# QTouchShield.net
KiCad netlist of a schematic drawn in EAGLE
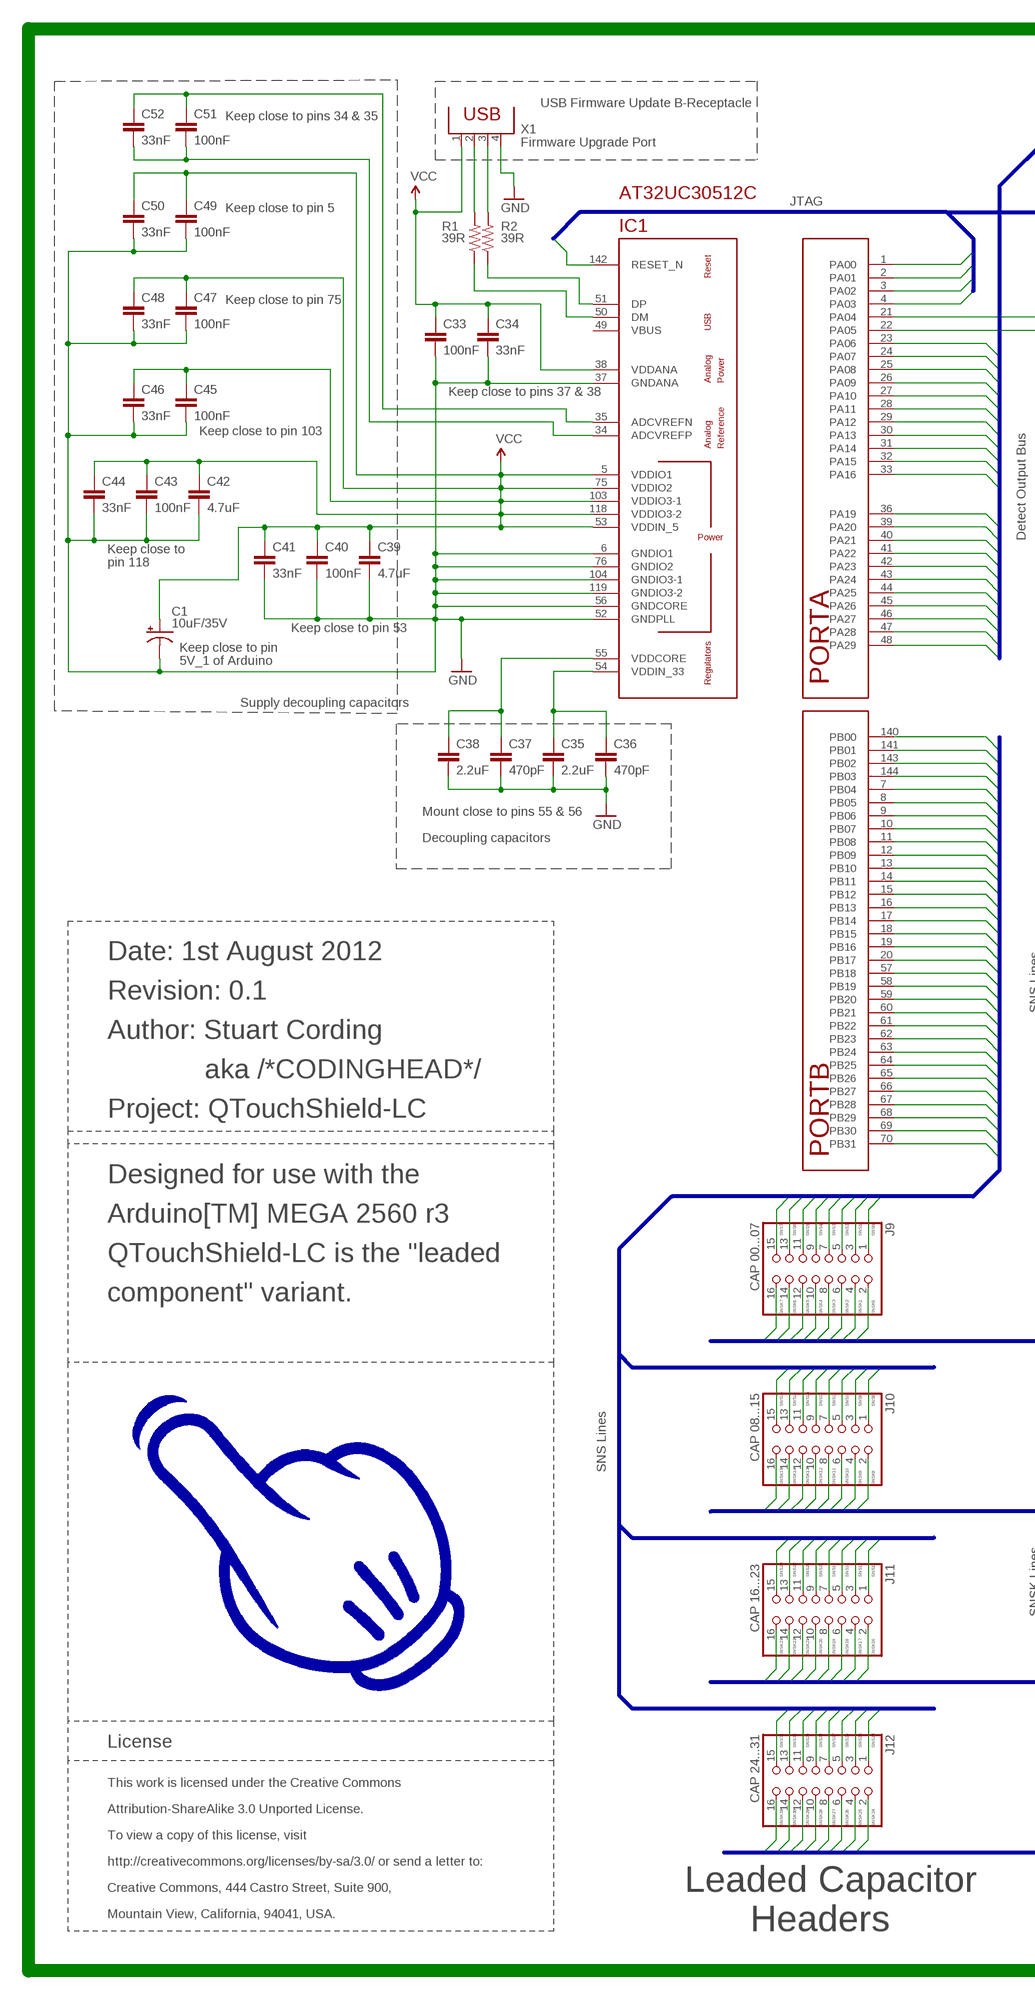
[diagram p0: schematic, sheet 1, part 1 of 2]
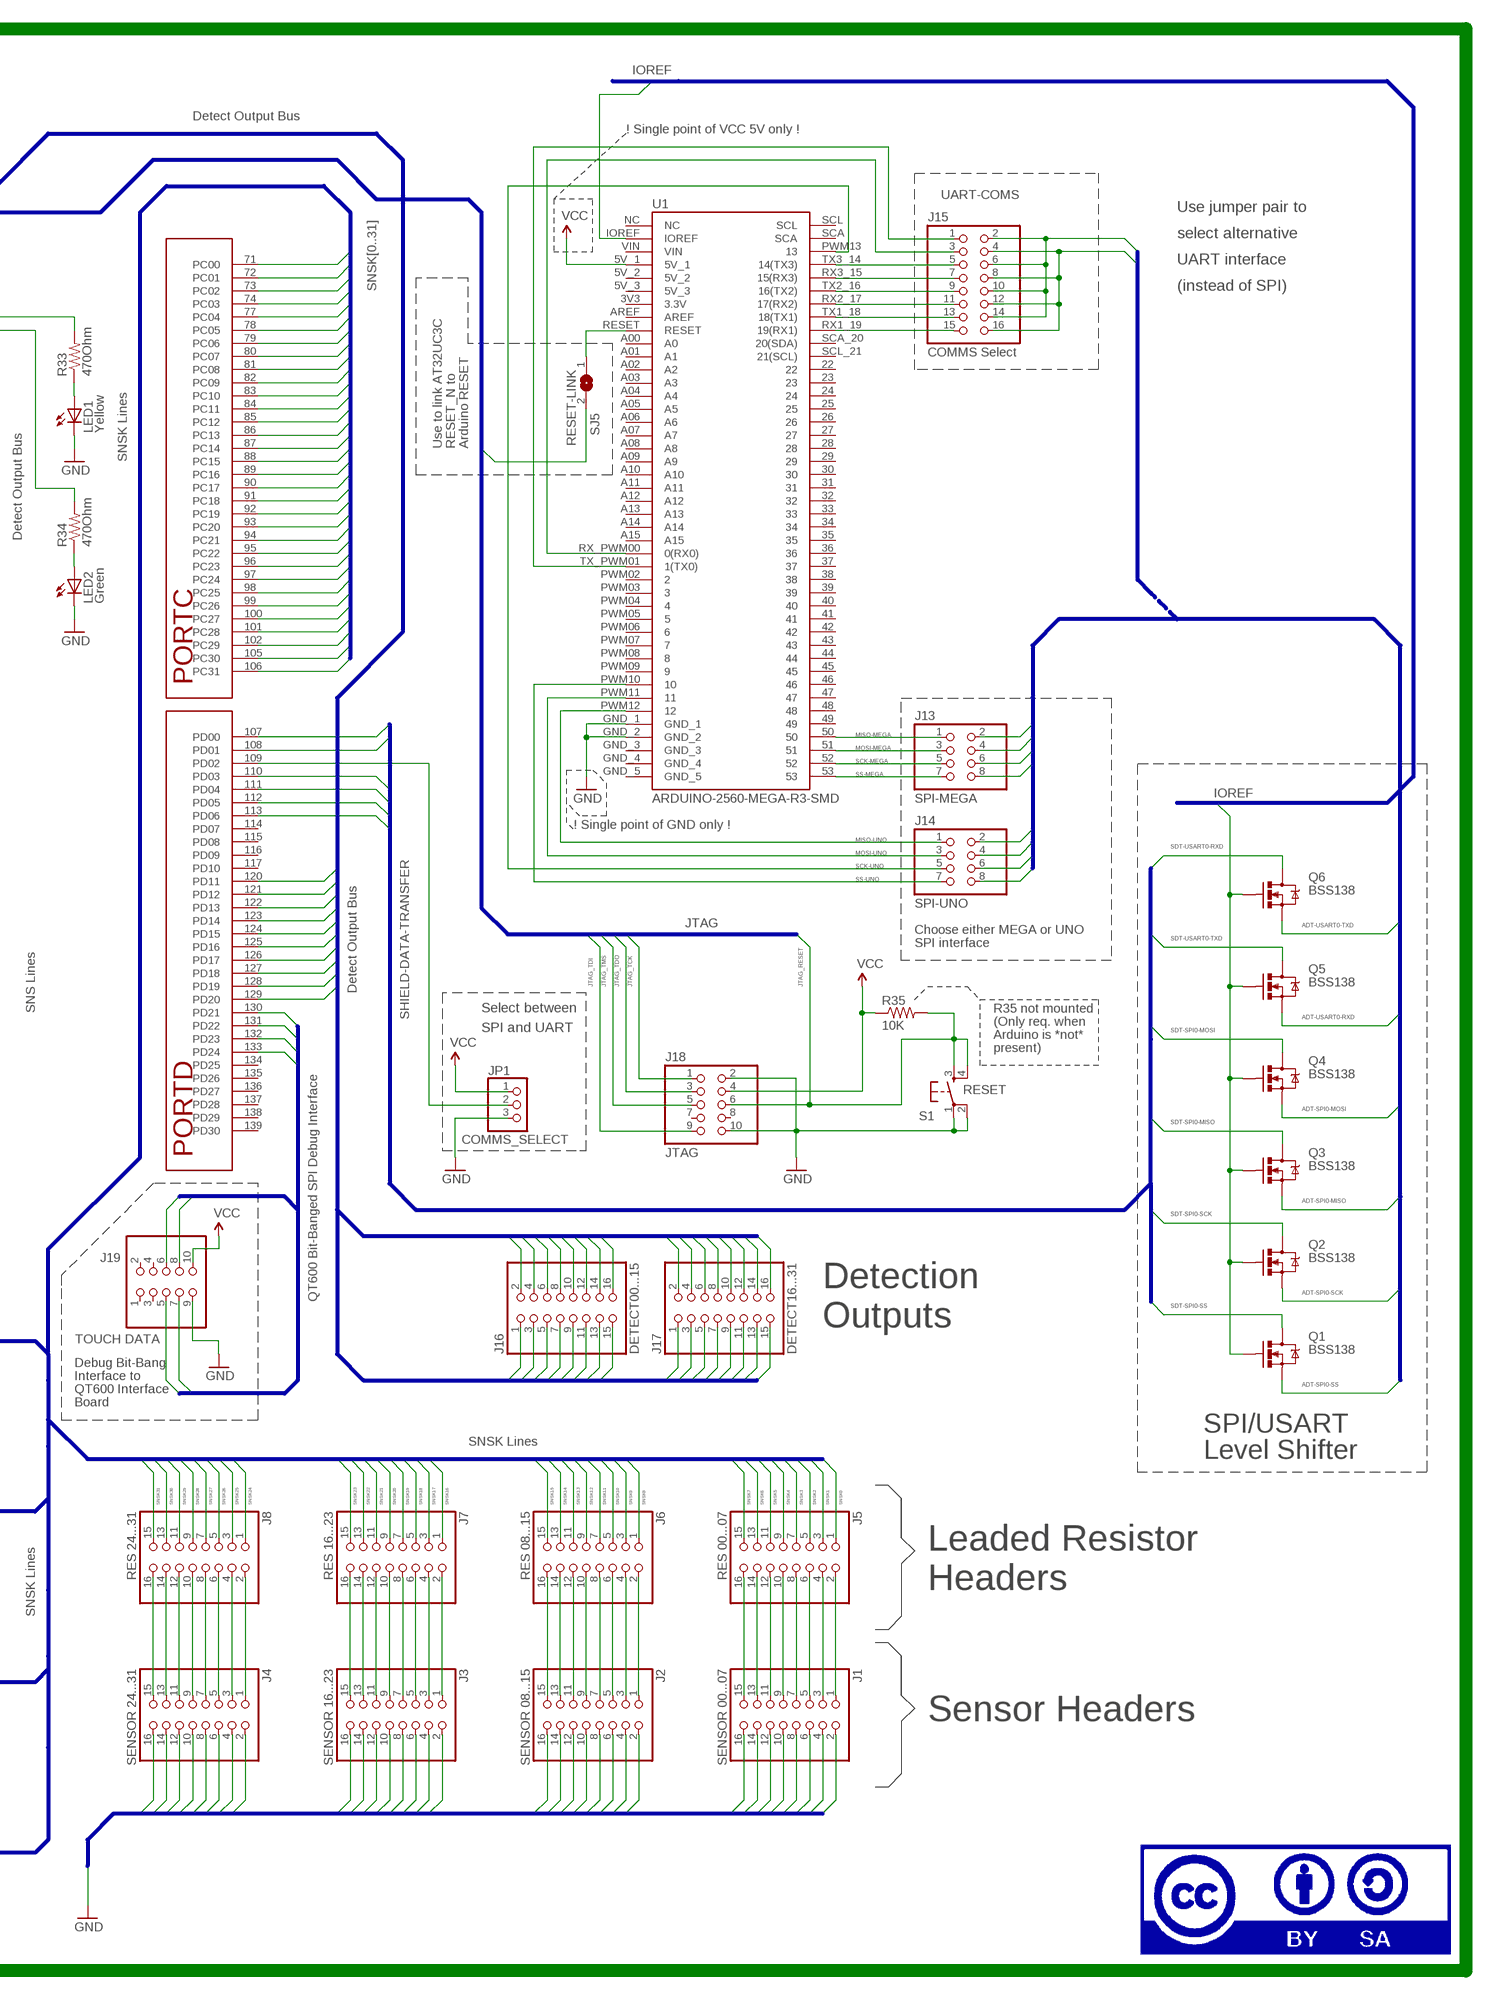
[diagram p1: schematic, sheet 1, part 2 of 2]

(export (version "E")
  (design (tool "Eeschema 10.0.6"))
  (components
    (comp (ref "C1")
      (value "10uF/35V")
      (footprint "eagle-import:PANASONIC_C")
      (libsource (lib "eagle-import") (part "CAP_POLC"))
    )
    (comp (ref "C33")
      (value "100nF")
      (footprint "eagle-import:0805")
      (libsource (lib "eagle-import") (part "CAP0805"))
    )
    (comp (ref "C34")
      (value "33nF")
      (footprint "eagle-import:0805")
      (libsource (lib "eagle-import") (part "CAP0805"))
    )
    (comp (ref "C35")
      (value "2.2uF")
      (footprint "eagle-import:1210")
      (libsource (lib "eagle-import") (part "CAP1210"))
    )
    (comp (ref "C36")
      (value "470pF")
      (footprint "eagle-import:0805")
      (libsource (lib "eagle-import") (part "CAP0805"))
    )
    (comp (ref "C37")
      (value "470pF")
      (footprint "eagle-import:0805")
      (libsource (lib "eagle-import") (part "CAP0805"))
    )
    (comp (ref "C38")
      (value "2.2uF")
      (footprint "eagle-import:1210")
      (libsource (lib "eagle-import") (part "CAP1210"))
    )
    (comp (ref "C39")
      (value "4.7uF")
      (footprint "eagle-import:1210")
      (libsource (lib "eagle-import") (part "CAP1210"))
    )
    (comp (ref "C40")
      (value "100nF")
      (footprint "eagle-import:0805")
      (libsource (lib "eagle-import") (part "CAP0805"))
    )
    (comp (ref "C41")
      (value "33nF")
      (footprint "eagle-import:0805")
      (libsource (lib "eagle-import") (part "CAP0805"))
    )
    (comp (ref "C42")
      (value "4.7uF")
      (footprint "eagle-import:1210")
      (libsource (lib "eagle-import") (part "CAP1210"))
    )
    (comp (ref "C43")
      (value "100nF")
      (footprint "eagle-import:0805")
      (libsource (lib "eagle-import") (part "CAP0805"))
    )
    (comp (ref "C44")
      (value "33nF")
      (footprint "eagle-import:0805")
      (libsource (lib "eagle-import") (part "CAP0805"))
    )
    (comp (ref "C45")
      (value "100nF")
      (footprint "eagle-import:0805")
      (libsource (lib "eagle-import") (part "CAP0805"))
    )
    (comp (ref "C46")
      (value "33nF")
      (footprint "eagle-import:0805")
      (libsource (lib "eagle-import") (part "CAP0805"))
    )
    (comp (ref "C47")
      (value "100nF")
      (footprint "eagle-import:0805")
      (libsource (lib "eagle-import") (part "CAP0805"))
    )
    (comp (ref "C48")
      (value "33nF")
      (footprint "eagle-import:0805")
      (libsource (lib "eagle-import") (part "CAP0805"))
    )
    (comp (ref "C49")
      (value "100nF")
      (footprint "eagle-import:0805")
      (libsource (lib "eagle-import") (part "CAP0805"))
    )
    (comp (ref "C50")
      (value "33nF")
      (footprint "eagle-import:0805")
      (libsource (lib "eagle-import") (part "CAP0805"))
    )
    (comp (ref "C51")
      (value "100nF")
      (footprint "eagle-import:0805")
      (libsource (lib "eagle-import") (part "CAP0805"))
    )
    (comp (ref "C52")
      (value "33nF")
      (footprint "eagle-import:0805")
      (libsource (lib "eagle-import") (part "CAP0805"))
    )
    (comp (ref "IC1")
      (value "AT32UC3C0512CJEDEC-MS-026")
      (footprint "eagle-import:LQFP144")
      (libsource (lib "eagle-import") (part "AT32UC3C0512CJEDEC-MS-026"))
    )
    (comp (ref "J1")
      (value "SENSOR 00...07")
      (footprint "eagle-import:2X8-V-MALE-SMT-HARWIN")
      (libsource (lib "eagle-import") (part "2X8-HEADERHARWIN-PIN-SMT"))
    )
    (comp (ref "J2")
      (value "SENSOR 08...15")
      (footprint "eagle-import:2X8-V-MALE-SMT-HARWIN")
      (libsource (lib "eagle-import") (part "2X8-HEADERHARWIN-PIN-SMT"))
    )
    (comp (ref "J3")
      (value "SENSOR 16...23")
      (footprint "eagle-import:2X8-V-MALE-SMT-HARWIN")
      (libsource (lib "eagle-import") (part "2X8-HEADERHARWIN-PIN-SMT"))
    )
    (comp (ref "J4")
      (value "SENSOR 24...31")
      (footprint "eagle-import:2X8-V-MALE-SMT-HARWIN")
      (libsource (lib "eagle-import") (part "2X8-HEADERHARWIN-PIN-SMT"))
    )
    (comp (ref "J5")
      (value "RES 00...07")
      (footprint "eagle-import:2X8-V-FEMALE-SMT-HARWIN")
      (libsource (lib "eagle-import") (part "2X8-HEADERHARWIN-RECEPTACLE-SMT"))
    )
    (comp (ref "J6")
      (value "RES 08...15")
      (footprint "eagle-import:2X8-V-FEMALE-SMT-HARWIN")
      (libsource (lib "eagle-import") (part "2X8-HEADERHARWIN-RECEPTACLE-SMT"))
    )
    (comp (ref "J7")
      (value "RES 16...23")
      (footprint "eagle-import:2X8-V-FEMALE-SMT-HARWIN")
      (libsource (lib "eagle-import") (part "2X8-HEADERHARWIN-RECEPTACLE-SMT"))
    )
    (comp (ref "J8")
      (value "RES 24...31")
      (footprint "eagle-import:2X8-V-FEMALE-SMT-HARWIN")
      (libsource (lib "eagle-import") (part "2X8-HEADERHARWIN-RECEPTACLE-SMT"))
    )
    (comp (ref "J9")
      (value "CAP 00...07")
      (footprint "eagle-import:2X8-V-FEMALE-SMT-HARWIN")
      (libsource (lib "eagle-import") (part "2X8-HEADERHARWIN-RECEPTACLE-SMT"))
    )
    (comp (ref "J10")
      (value "CAP 08...15")
      (footprint "eagle-import:2X8-V-FEMALE-SMT-HARWIN")
      (libsource (lib "eagle-import") (part "2X8-HEADERHARWIN-RECEPTACLE-SMT"))
    )
    (comp (ref "J11")
      (value "CAP 16...23")
      (footprint "eagle-import:2X8-V-FEMALE-SMT-HARWIN")
      (libsource (lib "eagle-import") (part "2X8-HEADERHARWIN-RECEPTACLE-SMT"))
    )
    (comp (ref "J12")
      (value "CAP 24...31")
      (footprint "eagle-import:2X8-V-FEMALE-SMT-HARWIN")
      (libsource (lib "eagle-import") (part "2X8-HEADERHARWIN-RECEPTACLE-SMT"))
    )
    (comp (ref "J13")
      (value "SPI-MEGA")
      (footprint "eagle-import:2X4-V-MALE-SMT-HARWIN")
      (libsource (lib "eagle-import") (part "2X4-HEADERSMT-MALE"))
    )
    (comp (ref "J14")
      (value "SPI-UNO")
      (footprint "eagle-import:2X4-V-MALE-SMT-HARWIN")
      (libsource (lib "eagle-import") (part "2X4-HEADERSMT-MALE"))
    )
    (comp (ref "J15")
      (value "COMMS Select")
      (footprint "eagle-import:2X8-V-MALE-SMT-HARWIN")
      (libsource (lib "eagle-import") (part "2X8-HEADERHARWIN-PIN-SMT"))
    )
    (comp (ref "J16")
      (value "DETECT00...15")
      (footprint "eagle-import:2X8-V-MALE-SMT-HARWIN")
      (libsource (lib "eagle-import") (part "2X8-HEADERHARWIN-PIN-SMT"))
    )
    (comp (ref "J17")
      (value "DETECT16...31")
      (footprint "eagle-import:2X8-V-MALE-SMT-HARWIN")
      (libsource (lib "eagle-import") (part "2X8-HEADERHARWIN-PIN-SMT"))
    )
    (comp (ref "J18")
      (value "JTAG")
      (footprint "eagle-import:2X5-V-MALE-SMT-HARWIN")
      (libsource (lib "eagle-import") (part "2X5-HEADERSMT"))
    )
    (comp (ref "J19")
      (value "TOUCH DATA")
      (footprint "eagle-import:2X5-V-MALE-SMT-HARWIN")
      (libsource (lib "eagle-import") (part "2X5-HEADERSMT"))
    )
    (comp (ref "JP1")
      (value "COMMS_SELECT")
      (footprint "eagle-import:1X03")
      (libsource (lib "eagle-import") (part "PINHD-1X3"))
    )
    (comp (ref "LED1")
      (value "Yellow")
      (footprint "eagle-import:LED-1206")
      (libsource (lib "eagle-import") (part "LED1206"))
    )
    (comp (ref "LED2")
      (value "Green")
      (footprint "eagle-import:LED-1206")
      (libsource (lib "eagle-import") (part "LED1206"))
    )
    (comp (ref "Q1")
      (value "BSS138")
      (footprint "eagle-import:SOT23-3")
      (libsource (lib "eagle-import") (part "MOSFET-NCHANNELSMD"))
    )
    (comp (ref "Q2")
      (value "BSS138")
      (footprint "eagle-import:SOT23-3")
      (libsource (lib "eagle-import") (part "MOSFET-NCHANNELSMD"))
    )
    (comp (ref "Q3")
      (value "BSS138")
      (footprint "eagle-import:SOT23-3")
      (libsource (lib "eagle-import") (part "MOSFET-NCHANNELSMD"))
    )
    (comp (ref "Q4")
      (value "BSS138")
      (footprint "eagle-import:SOT23-3")
      (libsource (lib "eagle-import") (part "MOSFET-NCHANNELSMD"))
    )
    (comp (ref "Q5")
      (value "BSS138")
      (footprint "eagle-import:SOT23-3")
      (libsource (lib "eagle-import") (part "MOSFET-NCHANNELSMD"))
    )
    (comp (ref "Q6")
      (value "BSS138")
      (footprint "eagle-import:SOT23-3")
      (libsource (lib "eagle-import") (part "MOSFET-NCHANNELSMD"))
    )
    (comp (ref "R1")
      (value "39R")
      (footprint "eagle-import:0805")
      (libsource (lib "eagle-import") (part "RESISTOR0805-RES"))
    )
    (comp (ref "R2")
      (value "39R")
      (footprint "eagle-import:0805")
      (libsource (lib "eagle-import") (part "RESISTOR0805-RES"))
    )
    (comp (ref "R33")
      (value "470Ohm")
      (footprint "eagle-import:0805")
      (libsource (lib "eagle-import") (part "RESISTOR0805-RES"))
    )
    (comp (ref "R34")
      (value "470Ohm")
      (footprint "eagle-import:0805")
      (libsource (lib "eagle-import") (part "RESISTOR0805-RES"))
    )
    (comp (ref "R35")
      (value "10K")
      (footprint "eagle-import:0805")
      (libsource (lib "eagle-import") (part "RESISTOR0805-RES"))
    )
    (comp (ref "S1")
      (value "RESET")
      (footprint "eagle-import:TACTILE_SWITCH_SMD")
      (libsource (lib "eagle-import") (part "TAC_SWITCHSMD"))
    )
    (comp (ref "SJ5")
      (value "RESET-LINK")
      (footprint "eagle-import:SJ")
      (libsource (lib "eagle-import") (part "SJ"))
    )
    (comp (ref "U1")
      (value "ARDUINO-2560-MEGA-R3-SMD")
      (footprint "eagle-import:ARDUINO-2560-R3-SMD")
      (libsource (lib "eagle-import") (part "ARDUINO-2560-MEGA-R3SMD-BOTTOMSMD"))
    )
    (comp (ref "X1")
      (value "Firmware Upgrade Port")
      (footprint "eagle-import:PN87520")
      (libsource (lib "eagle-import") (part "PN87520"))
    )
  )
  (nets
    (net (code "1") (name "/ADT-SPI0-MISO") (class "Default")
      (node (ref "J13") (pin "2") (pinfunction "2_2") (pintype "passive"))
      (node (ref "J14") (pin "2") (pinfunction "2_2") (pintype "passive"))
      (node (ref "Q3") (pin "2") (pinfunction "S_2") (pintype "passive"))
    )
    (net (code "2") (name "/ADT-SPI0-MOSI") (class "Default")
      (node (ref "J13") (pin "4") (pinfunction "4_4") (pintype "passive"))
      (node (ref "J14") (pin "4") (pinfunction "4_4") (pintype "passive"))
      (node (ref "Q4") (pin "2") (pinfunction "S_2") (pintype "passive"))
    )
    (net (code "3") (name "/ADT-SPI0-SCK") (class "Default")
      (node (ref "J13") (pin "6") (pinfunction "6_6") (pintype "passive"))
      (node (ref "J14") (pin "6") (pinfunction "6_6") (pintype "passive"))
      (node (ref "Q2") (pin "2") (pinfunction "S_2") (pintype "passive"))
    )
    (net (code "4") (name "/ADT-SPI0-SS") (class "Default")
      (node (ref "J13") (pin "8") (pinfunction "8_8") (pintype "passive"))
      (node (ref "J14") (pin "8") (pinfunction "8_8") (pintype "passive"))
      (node (ref "Q1") (pin "2") (pinfunction "S_2") (pintype "passive"))
    )
    (net (code "5") (name "/ADT-USART0-RXD") (class "Default")
      (node (ref "J15") (pin "12") (pinfunction "12_12") (pintype "passive"))
      (node (ref "J15") (pin "16") (pinfunction "16_16") (pintype "passive"))
      (node (ref "J15") (pin "4") (pinfunction "4_4") (pintype "passive"))
      (node (ref "J15") (pin "8") (pinfunction "8_8") (pintype "passive"))
      (node (ref "Q5") (pin "2") (pinfunction "S_2") (pintype "passive"))
    )
    (net (code "6") (name "/ADT-USART0-TXD") (class "Default")
      (node (ref "J15") (pin "10") (pinfunction "10_10") (pintype "passive"))
      (node (ref "J15") (pin "14") (pinfunction "14_14") (pintype "passive"))
      (node (ref "J15") (pin "2") (pinfunction "2_2") (pintype "passive"))
      (node (ref "J15") (pin "6") (pinfunction "6_6") (pintype "passive"))
      (node (ref "Q6") (pin "2") (pinfunction "S_2") (pintype "passive"))
    )
    (net (code "7") (name "/IOREF") (class "Default")
      (node (ref "Q1") (pin "1") (pinfunction "G_1") (pintype "passive"))
      (node (ref "Q2") (pin "1") (pinfunction "G_1") (pintype "passive"))
      (node (ref "Q3") (pin "1") (pinfunction "G_1") (pintype "passive"))
      (node (ref "Q4") (pin "1") (pinfunction "G_1") (pintype "passive"))
      (node (ref "Q5") (pin "1") (pinfunction "G_1") (pintype "passive"))
      (node (ref "Q6") (pin "1") (pinfunction "G_1") (pintype "passive"))
      (node (ref "U1") (pin "IOREF") (pinfunction "IOREF_IOREF") (pintype "bidirectional"))
    )
    (net (code "8") (name "/JTAG_RESET") (class "Default")
      (node (ref "IC1") (pin "142") (pinfunction "RESET_N_142") (pintype "input"))
      (node (ref "J18") (pin "6") (pinfunction "6_6") (pintype "passive"))
      (node (ref "R35") (pin "2") (pinfunction "2_2") (pintype "passive"))
      (node (ref "S1") (pin "3") (pinfunction "3_3") (pintype "passive"))
      (node (ref "S1") (pin "4") (pinfunction "4_4") (pintype "passive"))
      (node (ref "SJ5") (pin "2") (pinfunction "2_2") (pintype "passive"))
    )
    (net (code "9") (name "/JTAG_TCK") (class "Default")
      (node (ref "IC1") (pin "1") (pinfunction "PA00_1") (pintype "bidirectional"))
      (node (ref "J18") (pin "1") (pinfunction "1_1") (pintype "passive"))
    )
    (net (code "10") (name "/JTAG_TDI") (class "Default")
      (node (ref "IC1") (pin "2") (pinfunction "PA01_2") (pintype "bidirectional"))
      (node (ref "J18") (pin "9") (pinfunction "9_9") (pintype "passive"))
    )
    (net (code "11") (name "/JTAG_TDO") (class "Default")
      (node (ref "IC1") (pin "3") (pinfunction "PA02_3") (pintype "bidirectional"))
      (node (ref "J18") (pin "3") (pinfunction "3_3") (pintype "passive"))
    )
    (net (code "12") (name "/JTAG_TMS") (class "Default")
      (node (ref "IC1") (pin "4") (pinfunction "PA03_4") (pintype "bidirectional"))
      (node (ref "J18") (pin "5") (pinfunction "5_5") (pintype "passive"))
    )
    (net (code "13") (name "/MISO-MEGA") (class "Default")
      (node (ref "J13") (pin "1") (pinfunction "1_1") (pintype "passive"))
      (node (ref "U1") (pin "50") (pinfunction "50_50") (pintype "bidirectional"))
    )
    (net (code "14") (name "/MISO-UNO") (class "Default")
      (node (ref "J14") (pin "1") (pinfunction "1_1") (pintype "passive"))
      (node (ref "U1") (pin "PWM12") (pinfunction "12_PWM12") (pintype "bidirectional"))
    )
    (net (code "15") (name "/MOSI-MEGA") (class "Default")
      (node (ref "J13") (pin "3") (pinfunction "3_3") (pintype "passive"))
      (node (ref "U1") (pin "51") (pinfunction "51_51") (pintype "bidirectional"))
    )
    (net (code "16") (name "/MOSI-UNO") (class "Default")
      (node (ref "J14") (pin "3") (pinfunction "3_3") (pintype "passive"))
      (node (ref "U1") (pin "PWM11") (pinfunction "11_PWM11") (pintype "bidirectional"))
    )
    (net (code "17") (name "/SCK-MEGA") (class "Default")
      (node (ref "J13") (pin "5") (pinfunction "5_5") (pintype "passive"))
      (node (ref "U1") (pin "52") (pinfunction "52_52") (pintype "bidirectional"))
    )
    (net (code "18") (name "/SCK-UNO") (class "Default")
      (node (ref "J14") (pin "5") (pinfunction "5_5") (pintype "passive"))
      (node (ref "U1") (pin "PWM13") (pinfunction "13_PWM13") (pintype "bidirectional"))
    )
    (net (code "19") (name "/SDT-SPI0-MISO") (class "Default")
      (node (ref "IC1") (pin "112") (pinfunction "PD05_112") (pintype "bidirectional"))
      (node (ref "Q3") (pin "3") (pinfunction "D_3") (pintype "passive"))
    )
    (net (code "20") (name "/SDT-SPI0-MOSI") (class "Default")
      (node (ref "IC1") (pin "111") (pinfunction "PD04_111") (pintype "bidirectional"))
      (node (ref "Q4") (pin "3") (pinfunction "D_3") (pintype "passive"))
    )
    (net (code "21") (name "/SDT-SPI0-SCK") (class "Default")
      (node (ref "IC1") (pin "113") (pinfunction "PD06_113") (pintype "bidirectional"))
      (node (ref "Q2") (pin "3") (pinfunction "D_3") (pintype "passive"))
    )
    (net (code "22") (name "/SDT-SPI0-SS") (class "Default")
      (node (ref "IC1") (pin "110") (pinfunction "PD03_110") (pintype "bidirectional"))
      (node (ref "Q1") (pin "3") (pinfunction "D_3") (pintype "passive"))
    )
    (net (code "23") (name "/SDT-USART0-RXD") (class "Default")
      (node (ref "IC1") (pin "108") (pinfunction "PD01_108") (pintype "bidirectional"))
      (node (ref "Q6") (pin "3") (pinfunction "D_3") (pintype "passive"))
    )
    (net (code "24") (name "/SDT-USART0-TXD") (class "Default")
      (node (ref "IC1") (pin "107") (pinfunction "PD00_107") (pintype "bidirectional"))
      (node (ref "Q5") (pin "3") (pinfunction "D_3") (pintype "passive"))
    )
    (net (code "25") (name "/SHIELD-DETECT0") (class "Default")
      (node (ref "IC1") (pin "23") (pinfunction "PA06_23") (pintype "bidirectional"))
      (node (ref "J16") (pin "1") (pinfunction "1_1") (pintype "passive"))
    )
    (net (code "26") (name "/SHIELD-DETECT1") (class "Default")
      (node (ref "IC1") (pin "24") (pinfunction "PA07_24") (pintype "bidirectional"))
      (node (ref "J16") (pin "2") (pinfunction "2_2") (pintype "passive"))
    )
    (net (code "27") (name "/SHIELD-DETECT2") (class "Default")
      (node (ref "IC1") (pin "25") (pinfunction "PA08_25") (pintype "bidirectional"))
      (node (ref "J16") (pin "3") (pinfunction "3_3") (pintype "passive"))
    )
    (net (code "28") (name "/SHIELD-DETECT3") (class "Default")
      (node (ref "IC1") (pin "26") (pinfunction "PA09_26") (pintype "bidirectional"))
      (node (ref "J16") (pin "4") (pinfunction "4_4") (pintype "passive"))
    )
    (net (code "29") (name "/SHIELD-DETECT4") (class "Default")
      (node (ref "IC1") (pin "27") (pinfunction "PA10_27") (pintype "bidirectional"))
      (node (ref "J16") (pin "5") (pinfunction "5_5") (pintype "passive"))
    )
    (net (code "30") (name "/SHIELD-DETECT5") (class "Default")
      (node (ref "IC1") (pin "28") (pinfunction "PA11_28") (pintype "bidirectional"))
      (node (ref "J16") (pin "6") (pinfunction "6_6") (pintype "passive"))
    )
    (net (code "31") (name "/SHIELD-DETECT6") (class "Default")
      (node (ref "IC1") (pin "29") (pinfunction "PA12_29") (pintype "bidirectional"))
      (node (ref "J16") (pin "7") (pinfunction "7_7") (pintype "passive"))
    )
    (net (code "32") (name "/SHIELD-DETECT7") (class "Default")
      (node (ref "IC1") (pin "30") (pinfunction "PA13_30") (pintype "bidirectional"))
      (node (ref "J16") (pin "8") (pinfunction "8_8") (pintype "passive"))
    )
    (net (code "33") (name "/SHIELD-DETECT8") (class "Default")
      (node (ref "IC1") (pin "31") (pinfunction "PA14_31") (pintype "bidirectional"))
      (node (ref "J16") (pin "9") (pinfunction "9_9") (pintype "passive"))
    )
    (net (code "34") (name "/SHIELD-DETECT9") (class "Default")
      (node (ref "IC1") (pin "32") (pinfunction "PA15_32") (pintype "bidirectional"))
      (node (ref "J16") (pin "10") (pinfunction "10_10") (pintype "passive"))
    )
    (net (code "35") (name "/SHIELD-DETECT10") (class "Default")
      (node (ref "IC1") (pin "33") (pinfunction "PA16_33") (pintype "bidirectional"))
      (node (ref "J16") (pin "11") (pinfunction "11_11") (pintype "passive"))
    )
    (net (code "36") (name "/SHIELD-DETECT11") (class "Default")
      (node (ref "IC1") (pin "36") (pinfunction "PA19_36") (pintype "bidirectional"))
      (node (ref "J16") (pin "12") (pinfunction "12_12") (pintype "passive"))
    )
    (net (code "37") (name "/SHIELD-DETECT12") (class "Default")
      (node (ref "IC1") (pin "39") (pinfunction "PA20_39") (pintype "bidirectional"))
      (node (ref "J16") (pin "13") (pinfunction "13_13") (pintype "passive"))
    )
    (net (code "38") (name "/SHIELD-DETECT13") (class "Default")
      (node (ref "IC1") (pin "40") (pinfunction "PA21_40") (pintype "bidirectional"))
      (node (ref "J16") (pin "14") (pinfunction "14_14") (pintype "passive"))
    )
    (net (code "39") (name "/SHIELD-DETECT14") (class "Default")
      (node (ref "IC1") (pin "41") (pinfunction "PA22_41") (pintype "bidirectional"))
      (node (ref "J16") (pin "15") (pinfunction "15_15") (pintype "passive"))
    )
    (net (code "40") (name "/SHIELD-DETECT15") (class "Default")
      (node (ref "IC1") (pin "42") (pinfunction "PA23_42") (pintype "bidirectional"))
      (node (ref "J16") (pin "16") (pinfunction "16_16") (pintype "passive"))
    )
    (net (code "41") (name "/SHIELD-DETECT16") (class "Default")
      (node (ref "IC1") (pin "43") (pinfunction "PA24_43") (pintype "bidirectional"))
      (node (ref "J17") (pin "15") (pinfunction "15_15") (pintype "passive"))
    )
    (net (code "42") (name "/SHIELD-DETECT17") (class "Default")
      (node (ref "IC1") (pin "44") (pinfunction "PA25_44") (pintype "bidirectional"))
      (node (ref "J17") (pin "16") (pinfunction "16_16") (pintype "passive"))
    )
    (net (code "43") (name "/SHIELD-DETECT18") (class "Default")
      (node (ref "IC1") (pin "45") (pinfunction "PA26_45") (pintype "bidirectional"))
      (node (ref "J17") (pin "13") (pinfunction "13_13") (pintype "passive"))
    )
    (net (code "44") (name "/SHIELD-DETECT19") (class "Default")
      (node (ref "IC1") (pin "46") (pinfunction "PA27_46") (pintype "bidirectional"))
      (node (ref "J17") (pin "14") (pinfunction "14_14") (pintype "passive"))
    )
    (net (code "45") (name "/SHIELD-DETECT20") (class "Default")
      (node (ref "IC1") (pin "47") (pinfunction "PA28_47") (pintype "bidirectional"))
      (node (ref "J17") (pin "11") (pinfunction "11_11") (pintype "passive"))
    )
    (net (code "46") (name "/SHIELD-DETECT21") (class "Default")
      (node (ref "IC1") (pin "48") (pinfunction "PA29_48") (pintype "bidirectional"))
      (node (ref "J17") (pin "12") (pinfunction "12_12") (pintype "passive"))
    )
    (net (code "47") (name "/SHIELD-DETECT22") (class "Default")
      (node (ref "IC1") (pin "120") (pinfunction "PD11_120") (pintype "bidirectional"))
      (node (ref "J17") (pin "9") (pinfunction "9_9") (pintype "passive"))
    )
    (net (code "48") (name "/SHIELD-DETECT23") (class "Default")
      (node (ref "IC1") (pin "121") (pinfunction "PD12_121") (pintype "bidirectional"))
      (node (ref "J17") (pin "10") (pinfunction "10_10") (pintype "passive"))
    )
    (net (code "49") (name "/SHIELD-DETECT24") (class "Default")
      (node (ref "IC1") (pin "122") (pinfunction "PD13_122") (pintype "bidirectional"))
      (node (ref "J17") (pin "7") (pinfunction "7_7") (pintype "passive"))
    )
    (net (code "50") (name "/SHIELD-DETECT25") (class "Default")
      (node (ref "IC1") (pin "123") (pinfunction "PD14_123") (pintype "bidirectional"))
      (node (ref "J17") (pin "8") (pinfunction "8_8") (pintype "passive"))
    )
    (net (code "51") (name "/SHIELD-DETECT26") (class "Default")
      (node (ref "IC1") (pin "124") (pinfunction "PD15_124") (pintype "bidirectional"))
      (node (ref "J17") (pin "5") (pinfunction "5_5") (pintype "passive"))
    )
    (net (code "52") (name "/SHIELD-DETECT27") (class "Default")
      (node (ref "IC1") (pin "125") (pinfunction "PD16_125") (pintype "bidirectional"))
      (node (ref "J17") (pin "6") (pinfunction "6_6") (pintype "passive"))
    )
    (net (code "53") (name "/SHIELD-DETECT28") (class "Default")
      (node (ref "IC1") (pin "126") (pinfunction "PD17_126") (pintype "bidirectional"))
      (node (ref "J17") (pin "3") (pinfunction "3_3") (pintype "passive"))
    )
    (net (code "54") (name "/SHIELD-DETECT29") (class "Default")
      (node (ref "IC1") (pin "127") (pinfunction "PD18_127") (pintype "bidirectional"))
      (node (ref "J17") (pin "4") (pinfunction "4_4") (pintype "passive"))
    )
    (net (code "55") (name "/SHIELD-DETECT30") (class "Default")
      (node (ref "IC1") (pin "128") (pinfunction "PD19_128") (pintype "bidirectional"))
      (node (ref "J17") (pin "1") (pinfunction "1_1") (pintype "passive"))
    )
    (net (code "56") (name "/SHIELD-DETECT31") (class "Default")
      (node (ref "IC1") (pin "129") (pinfunction "PD20_129") (pintype "bidirectional"))
      (node (ref "J17") (pin "2") (pinfunction "2_2") (pintype "passive"))
    )
    (net (code "57") (name "/SNS0") (class "Default")
      (node (ref "IC1") (pin "140") (pinfunction "PB00_140") (pintype "bidirectional"))
      (node (ref "J9") (pin "1") (pinfunction "1_1") (pintype "passive"))
    )
    (net (code "58") (name "/SNS1") (class "Default")
      (node (ref "IC1") (pin "141") (pinfunction "PB01_141") (pintype "bidirectional"))
      (node (ref "J9") (pin "3") (pinfunction "3_3") (pintype "passive"))
    )
    (net (code "59") (name "/SNS2") (class "Default")
      (node (ref "IC1") (pin "143") (pinfunction "PB02_143") (pintype "bidirectional"))
      (node (ref "J9") (pin "5") (pinfunction "5_5") (pintype "passive"))
    )
    (net (code "60") (name "/SNS3") (class "Default")
      (node (ref "IC1") (pin "144") (pinfunction "PB03_144") (pintype "bidirectional"))
      (node (ref "J9") (pin "7") (pinfunction "7_7") (pintype "passive"))
    )
    (net (code "61") (name "/SNS4") (class "Default")
      (node (ref "IC1") (pin "7") (pinfunction "PB04_7") (pintype "bidirectional"))
      (node (ref "J9") (pin "9") (pinfunction "9_9") (pintype "passive"))
    )
    (net (code "62") (name "/SNS5") (class "Default")
      (node (ref "IC1") (pin "8") (pinfunction "PB05_8") (pintype "bidirectional"))
      (node (ref "J9") (pin "11") (pinfunction "11_11") (pintype "passive"))
    )
    (net (code "63") (name "/SNS6") (class "Default")
      (node (ref "IC1") (pin "9") (pinfunction "PB06_9") (pintype "bidirectional"))
      (node (ref "J9") (pin "13") (pinfunction "13_13") (pintype "passive"))
    )
    (net (code "64") (name "/SNS7") (class "Default")
      (node (ref "IC1") (pin "10") (pinfunction "PB07_10") (pintype "bidirectional"))
      (node (ref "J9") (pin "15") (pinfunction "15_15") (pintype "passive"))
    )
    (net (code "65") (name "/SNS8") (class "Default")
      (node (ref "IC1") (pin "11") (pinfunction "PB08_11") (pintype "bidirectional"))
      (node (ref "J10") (pin "1") (pinfunction "1_1") (pintype "passive"))
    )
    (net (code "66") (name "/SNS9") (class "Default")
      (node (ref "IC1") (pin "12") (pinfunction "PB09_12") (pintype "bidirectional"))
      (node (ref "J10") (pin "3") (pinfunction "3_3") (pintype "passive"))
    )
    (net (code "67") (name "/SNS10") (class "Default")
      (node (ref "IC1") (pin "13") (pinfunction "PB10_13") (pintype "bidirectional"))
      (node (ref "J10") (pin "5") (pinfunction "5_5") (pintype "passive"))
    )
    (net (code "68") (name "/SNS11") (class "Default")
      (node (ref "IC1") (pin "14") (pinfunction "PB11_14") (pintype "bidirectional"))
      (node (ref "J10") (pin "7") (pinfunction "7_7") (pintype "passive"))
    )
    (net (code "69") (name "/SNS12") (class "Default")
      (node (ref "IC1") (pin "15") (pinfunction "PB12_15") (pintype "bidirectional"))
      (node (ref "J10") (pin "9") (pinfunction "9_9") (pintype "passive"))
    )
    (net (code "70") (name "/SNS13") (class "Default")
      (node (ref "IC1") (pin "16") (pinfunction "PB13_16") (pintype "bidirectional"))
      (node (ref "J10") (pin "11") (pinfunction "11_11") (pintype "passive"))
    )
    (net (code "71") (name "/SNS14") (class "Default")
      (node (ref "IC1") (pin "17") (pinfunction "PB14_17") (pintype "bidirectional"))
      (node (ref "J10") (pin "13") (pinfunction "13_13") (pintype "passive"))
    )
    (net (code "72") (name "/SNS15") (class "Default")
      (node (ref "IC1") (pin "18") (pinfunction "PB15_18") (pintype "bidirectional"))
      (node (ref "J10") (pin "15") (pinfunction "15_15") (pintype "passive"))
    )
    (net (code "73") (name "/SNS16") (class "Default")
      (node (ref "IC1") (pin "19") (pinfunction "PB16_19") (pintype "bidirectional"))
      (node (ref "J11") (pin "1") (pinfunction "1_1") (pintype "passive"))
    )
    (net (code "74") (name "/SNS17") (class "Default")
      (node (ref "IC1") (pin "20") (pinfunction "PB17_20") (pintype "bidirectional"))
      (node (ref "J11") (pin "3") (pinfunction "3_3") (pintype "passive"))
    )
    (net (code "75") (name "/SNS18") (class "Default")
      (node (ref "IC1") (pin "57") (pinfunction "PB18_57") (pintype "bidirectional"))
      (node (ref "J11") (pin "5") (pinfunction "5_5") (pintype "passive"))
    )
    (net (code "76") (name "/SNS19") (class "Default")
      (node (ref "IC1") (pin "58") (pinfunction "PB19_58") (pintype "bidirectional"))
      (node (ref "J11") (pin "7") (pinfunction "7_7") (pintype "passive"))
    )
    (net (code "77") (name "/SNS20") (class "Default")
      (node (ref "IC1") (pin "59") (pinfunction "PB20_59") (pintype "bidirectional"))
      (node (ref "J11") (pin "9") (pinfunction "9_9") (pintype "passive"))
    )
    (net (code "78") (name "/SNS21") (class "Default")
      (node (ref "IC1") (pin "60") (pinfunction "PB21_60") (pintype "bidirectional"))
      (node (ref "J11") (pin "11") (pinfunction "11_11") (pintype "passive"))
    )
    (net (code "79") (name "/SNS22") (class "Default")
      (node (ref "IC1") (pin "61") (pinfunction "PB22_61") (pintype "bidirectional"))
      (node (ref "J11") (pin "13") (pinfunction "13_13") (pintype "passive"))
    )
    (net (code "80") (name "/SNS23") (class "Default")
      (node (ref "IC1") (pin "62") (pinfunction "PB23_62") (pintype "bidirectional"))
      (node (ref "J11") (pin "15") (pinfunction "15_15") (pintype "passive"))
    )
    (net (code "81") (name "/SNS24") (class "Default")
      (node (ref "IC1") (pin "63") (pinfunction "PB24_63") (pintype "bidirectional"))
      (node (ref "J12") (pin "1") (pinfunction "1_1") (pintype "passive"))
    )
    (net (code "82") (name "/SNS25") (class "Default")
      (node (ref "IC1") (pin "64") (pinfunction "PB25_64") (pintype "bidirectional"))
      (node (ref "J12") (pin "3") (pinfunction "3_3") (pintype "passive"))
    )
    (net (code "83") (name "/SNS26") (class "Default")
      (node (ref "IC1") (pin "65") (pinfunction "PB26_65") (pintype "bidirectional"))
      (node (ref "J12") (pin "5") (pinfunction "5_5") (pintype "passive"))
    )
    (net (code "84") (name "/SNS27") (class "Default")
      (node (ref "IC1") (pin "66") (pinfunction "PB27_66") (pintype "bidirectional"))
      (node (ref "J12") (pin "7") (pinfunction "7_7") (pintype "passive"))
    )
    (net (code "85") (name "/SNS28") (class "Default")
      (node (ref "IC1") (pin "67") (pinfunction "PB28_67") (pintype "bidirectional"))
      (node (ref "J12") (pin "9") (pinfunction "9_9") (pintype "passive"))
    )
    (net (code "86") (name "/SNS29") (class "Default")
      (node (ref "IC1") (pin "68") (pinfunction "PB29_68") (pintype "bidirectional"))
      (node (ref "J12") (pin "11") (pinfunction "11_11") (pintype "passive"))
    )
    (net (code "87") (name "/SNS30") (class "Default")
      (node (ref "IC1") (pin "69") (pinfunction "PB30_69") (pintype "bidirectional"))
      (node (ref "J12") (pin "13") (pinfunction "13_13") (pintype "passive"))
    )
    (net (code "88") (name "/SNS31") (class "Default")
      (node (ref "IC1") (pin "70") (pinfunction "PB31_70") (pintype "bidirectional"))
      (node (ref "J12") (pin "15") (pinfunction "15_15") (pintype "passive"))
    )
    (net (code "89") (name "/SNSK0") (class "Default")
      (node (ref "IC1") (pin "71") (pinfunction "PC00_71") (pintype "bidirectional"))
      (node (ref "J5") (pin "1") (pinfunction "1_1") (pintype "passive"))
      (node (ref "J9") (pin "2") (pinfunction "2_2") (pintype "passive"))
    )
    (net (code "90") (name "/SNSK1") (class "Default")
      (node (ref "IC1") (pin "72") (pinfunction "PC01_72") (pintype "bidirectional"))
      (node (ref "J5") (pin "3") (pinfunction "3_3") (pintype "passive"))
      (node (ref "J9") (pin "4") (pinfunction "4_4") (pintype "passive"))
    )
    (net (code "91") (name "/SNSK2") (class "Default")
      (node (ref "IC1") (pin "73") (pinfunction "PC02_73") (pintype "bidirectional"))
      (node (ref "J5") (pin "5") (pinfunction "5_5") (pintype "passive"))
      (node (ref "J9") (pin "6") (pinfunction "6_6") (pintype "passive"))
    )
    (net (code "92") (name "/SNSK3") (class "Default")
      (node (ref "IC1") (pin "74") (pinfunction "PC03_74") (pintype "bidirectional"))
      (node (ref "J5") (pin "7") (pinfunction "7_7") (pintype "passive"))
      (node (ref "J9") (pin "8") (pinfunction "8_8") (pintype "passive"))
    )
    (net (code "93") (name "/SNSK4") (class "Default")
      (node (ref "IC1") (pin "77") (pinfunction "PC04_77") (pintype "bidirectional"))
      (node (ref "J5") (pin "9") (pinfunction "9_9") (pintype "passive"))
      (node (ref "J9") (pin "10") (pinfunction "10_10") (pintype "passive"))
    )
    (net (code "94") (name "/SNSK5") (class "Default")
      (node (ref "IC1") (pin "78") (pinfunction "PC05_78") (pintype "bidirectional"))
      (node (ref "J5") (pin "11") (pinfunction "11_11") (pintype "passive"))
      (node (ref "J9") (pin "12") (pinfunction "12_12") (pintype "passive"))
    )
    (net (code "95") (name "/SNSK6") (class "Default")
      (node (ref "IC1") (pin "79") (pinfunction "PC06_79") (pintype "bidirectional"))
      (node (ref "J5") (pin "13") (pinfunction "13_13") (pintype "passive"))
      (node (ref "J9") (pin "14") (pinfunction "14_14") (pintype "passive"))
    )
    (net (code "96") (name "/SNSK7") (class "Default")
      (node (ref "IC1") (pin "80") (pinfunction "PC07_80") (pintype "bidirectional"))
      (node (ref "J5") (pin "15") (pinfunction "15_15") (pintype "passive"))
      (node (ref "J9") (pin "16") (pinfunction "16_16") (pintype "passive"))
    )
    (net (code "97") (name "/SNSK8") (class "Default")
      (node (ref "IC1") (pin "81") (pinfunction "PC08_81") (pintype "bidirectional"))
      (node (ref "J10") (pin "2") (pinfunction "2_2") (pintype "passive"))
      (node (ref "J6") (pin "1") (pinfunction "1_1") (pintype "passive"))
    )
    (net (code "98") (name "/SNSK9") (class "Default")
      (node (ref "IC1") (pin "82") (pinfunction "PC09_82") (pintype "bidirectional"))
      (node (ref "J10") (pin "4") (pinfunction "4_4") (pintype "passive"))
      (node (ref "J6") (pin "3") (pinfunction "3_3") (pintype "passive"))
    )
    (net (code "99") (name "/SNSK10") (class "Default")
      (node (ref "IC1") (pin "83") (pinfunction "PC10_83") (pintype "bidirectional"))
      (node (ref "J10") (pin "6") (pinfunction "6_6") (pintype "passive"))
      (node (ref "J6") (pin "5") (pinfunction "5_5") (pintype "passive"))
    )
    (net (code "100") (name "/SNSK11") (class "Default")
      (node (ref "IC1") (pin "84") (pinfunction "PC11_84") (pintype "bidirectional"))
      (node (ref "J10") (pin "8") (pinfunction "8_8") (pintype "passive"))
      (node (ref "J6") (pin "7") (pinfunction "7_7") (pintype "passive"))
    )
    (net (code "101") (name "/SNSK12") (class "Default")
      (node (ref "IC1") (pin "85") (pinfunction "PC12_85") (pintype "bidirectional"))
      (node (ref "J10") (pin "10") (pinfunction "10_10") (pintype "passive"))
      (node (ref "J6") (pin "9") (pinfunction "9_9") (pintype "passive"))
    )
    (net (code "102") (name "/SNSK13") (class "Default")
      (node (ref "IC1") (pin "86") (pinfunction "PC13_86") (pintype "bidirectional"))
      (node (ref "J10") (pin "12") (pinfunction "12_12") (pintype "passive"))
      (node (ref "J6") (pin "11") (pinfunction "11_11") (pintype "passive"))
    )
    (net (code "103") (name "/SNSK14") (class "Default")
      (node (ref "IC1") (pin "87") (pinfunction "PC14_87") (pintype "bidirectional"))
      (node (ref "J10") (pin "14") (pinfunction "14_14") (pintype "passive"))
      (node (ref "J6") (pin "13") (pinfunction "13_13") (pintype "passive"))
    )
    (net (code "104") (name "/SNSK15") (class "Default")
      (node (ref "IC1") (pin "88") (pinfunction "PC15_88") (pintype "bidirectional"))
      (node (ref "J10") (pin "16") (pinfunction "16_16") (pintype "passive"))
      (node (ref "J6") (pin "15") (pinfunction "15_15") (pintype "passive"))
    )
    (net (code "105") (name "/SNSK16") (class "Default")
      (node (ref "IC1") (pin "89") (pinfunction "PC16_89") (pintype "bidirectional"))
      (node (ref "J11") (pin "2") (pinfunction "2_2") (pintype "passive"))
      (node (ref "J7") (pin "1") (pinfunction "1_1") (pintype "passive"))
    )
    (net (code "106") (name "/SNSK17") (class "Default")
      (node (ref "IC1") (pin "90") (pinfunction "PC17_90") (pintype "bidirectional"))
      (node (ref "J11") (pin "4") (pinfunction "4_4") (pintype "passive"))
      (node (ref "J7") (pin "3") (pinfunction "3_3") (pintype "passive"))
    )
    (net (code "107") (name "/SNSK18") (class "Default")
      (node (ref "IC1") (pin "91") (pinfunction "PC18_91") (pintype "bidirectional"))
      (node (ref "J11") (pin "6") (pinfunction "6_6") (pintype "passive"))
      (node (ref "J7") (pin "5") (pinfunction "5_5") (pintype "passive"))
    )
    (net (code "108") (name "/SNSK19") (class "Default")
      (node (ref "IC1") (pin "92") (pinfunction "PC19_92") (pintype "bidirectional"))
      (node (ref "J11") (pin "8") (pinfunction "8_8") (pintype "passive"))
      (node (ref "J7") (pin "7") (pinfunction "7_7") (pintype "passive"))
    )
    (net (code "109") (name "/SNSK20") (class "Default")
      (node (ref "IC1") (pin "93") (pinfunction "PC20_93") (pintype "bidirectional"))
      (node (ref "J11") (pin "10") (pinfunction "10_10") (pintype "passive"))
      (node (ref "J7") (pin "9") (pinfunction "9_9") (pintype "passive"))
    )
    (net (code "110") (name "/SNSK21") (class "Default")
      (node (ref "IC1") (pin "94") (pinfunction "PC21_94") (pintype "bidirectional"))
      (node (ref "J11") (pin "12") (pinfunction "12_12") (pintype "passive"))
      (node (ref "J7") (pin "11") (pinfunction "11_11") (pintype "passive"))
    )
    (net (code "111") (name "/SNSK22") (class "Default")
      (node (ref "IC1") (pin "95") (pinfunction "PC22_95") (pintype "bidirectional"))
      (node (ref "J11") (pin "14") (pinfunction "14_14") (pintype "passive"))
      (node (ref "J7") (pin "13") (pinfunction "13_13") (pintype "passive"))
    )
    (net (code "112") (name "/SNSK23") (class "Default")
      (node (ref "IC1") (pin "96") (pinfunction "PC23_96") (pintype "bidirectional"))
      (node (ref "J11") (pin "16") (pinfunction "16_16") (pintype "passive"))
      (node (ref "J7") (pin "15") (pinfunction "15_15") (pintype "passive"))
    )
    (net (code "113") (name "/SNSK24") (class "Default")
      (node (ref "IC1") (pin "97") (pinfunction "PC24_97") (pintype "bidirectional"))
      (node (ref "J12") (pin "2") (pinfunction "2_2") (pintype "passive"))
      (node (ref "J8") (pin "1") (pinfunction "1_1") (pintype "passive"))
    )
    (net (code "114") (name "/SNSK25") (class "Default")
      (node (ref "IC1") (pin "98") (pinfunction "PC25_98") (pintype "bidirectional"))
      (node (ref "J12") (pin "4") (pinfunction "4_4") (pintype "passive"))
      (node (ref "J8") (pin "3") (pinfunction "3_3") (pintype "passive"))
    )
    (net (code "115") (name "/SNSK26") (class "Default")
      (node (ref "IC1") (pin "99") (pinfunction "PC26_99") (pintype "bidirectional"))
      (node (ref "J12") (pin "6") (pinfunction "6_6") (pintype "passive"))
      (node (ref "J8") (pin "5") (pinfunction "5_5") (pintype "passive"))
    )
    (net (code "116") (name "/SNSK27") (class "Default")
      (node (ref "IC1") (pin "100") (pinfunction "PC27_100") (pintype "bidirectional"))
      (node (ref "J12") (pin "8") (pinfunction "8_8") (pintype "passive"))
      (node (ref "J8") (pin "7") (pinfunction "7_7") (pintype "passive"))
    )
    (net (code "117") (name "/SNSK28") (class "Default")
      (node (ref "IC1") (pin "101") (pinfunction "PC28_101") (pintype "bidirectional"))
      (node (ref "J12") (pin "10") (pinfunction "10_10") (pintype "passive"))
      (node (ref "J8") (pin "9") (pinfunction "9_9") (pintype "passive"))
    )
    (net (code "118") (name "/SNSK29") (class "Default")
      (node (ref "IC1") (pin "102") (pinfunction "PC29_102") (pintype "bidirectional"))
      (node (ref "J12") (pin "12") (pinfunction "12_12") (pintype "passive"))
      (node (ref "J8") (pin "11") (pinfunction "11_11") (pintype "passive"))
    )
    (net (code "119") (name "/SNSK30") (class "Default")
      (node (ref "IC1") (pin "105") (pinfunction "PC30_105") (pintype "bidirectional"))
      (node (ref "J12") (pin "14") (pinfunction "14_14") (pintype "passive"))
      (node (ref "J8") (pin "13") (pinfunction "13_13") (pintype "passive"))
    )
    (net (code "120") (name "/SNSK31") (class "Default")
      (node (ref "IC1") (pin "106") (pinfunction "PC31_106") (pintype "bidirectional"))
      (node (ref "J12") (pin "16") (pinfunction "16_16") (pintype "passive"))
      (node (ref "J8") (pin "15") (pinfunction "15_15") (pintype "passive"))
    )
    (net (code "122") (name "/SS-MEGA") (class "Default")
      (node (ref "J13") (pin "7") (pinfunction "7_7") (pintype "passive"))
      (node (ref "U1") (pin "53") (pinfunction "53_53") (pintype "bidirectional"))
    )
    (net (code "123") (name "/SS-UNO") (class "Default")
      (node (ref "J14") (pin "7") (pinfunction "7_7") (pintype "passive"))
      (node (ref "U1") (pin "PWM10") (pinfunction "10_PWM10") (pintype "bidirectional"))
    )
    (net (code "124") (name "/TOUCH_DATA-MISO") (class "Default")
      (node (ref "IC1") (pin "133") (pinfunction "PD24_133") (pintype "bidirectional"))
      (node (ref "J19") (pin "7") (pinfunction "7_7") (pintype "passive"))
    )
    (net (code "125") (name "/TOUCH_DATA-MOSI") (class "Default")
      (node (ref "IC1") (pin "132") (pinfunction "PD23_132") (pintype "bidirectional"))
      (node (ref "J19") (pin "6") (pinfunction "6_6") (pintype "passive"))
    )
    (net (code "126") (name "/TOUCH_DATA-SCK") (class "Default")
      (node (ref "IC1") (pin "131") (pinfunction "PD22_131") (pintype "bidirectional"))
      (node (ref "J19") (pin "8") (pinfunction "8_8") (pintype "passive"))
    )
    (net (code "127") (name "/TOUCH_DATA-SS") (class "Default")
      (node (ref "IC1") (pin "130") (pinfunction "PD21_130") (pintype "bidirectional"))
      (node (ref "J19") (pin "5") (pinfunction "5_5") (pintype "passive"))
    )
    (net (code "129") (name "GND") (class "Default")
      (node (ref "C1") (pin "-") (pinfunction "-_-") (pintype "passive"))
      (node (ref "C33") (pin "2") (pinfunction "2_2") (pintype "passive"))
      (node (ref "C34") (pin "2") (pinfunction "2_2") (pintype "passive"))
      (node (ref "C35") (pin "2") (pinfunction "2_2") (pintype "passive"))
      (node (ref "C36") (pin "2") (pinfunction "2_2") (pintype "passive"))
      (node (ref "C37") (pin "2") (pinfunction "2_2") (pintype "passive"))
      (node (ref "C38") (pin "2") (pinfunction "2_2") (pintype "passive"))
      (node (ref "C39") (pin "2") (pinfunction "2_2") (pintype "passive"))
      (node (ref "C40") (pin "2") (pinfunction "2_2") (pintype "passive"))
      (node (ref "C41") (pin "2") (pinfunction "2_2") (pintype "passive"))
      (node (ref "C42") (pin "2") (pinfunction "2_2") (pintype "passive"))
      (node (ref "C43") (pin "2") (pinfunction "2_2") (pintype "passive"))
      (node (ref "C44") (pin "2") (pinfunction "2_2") (pintype "passive"))
      (node (ref "C45") (pin "2") (pinfunction "2_2") (pintype "passive"))
      (node (ref "C46") (pin "2") (pinfunction "2_2") (pintype "passive"))
      (node (ref "C47") (pin "2") (pinfunction "2_2") (pintype "passive"))
      (node (ref "C48") (pin "2") (pinfunction "2_2") (pintype "passive"))
      (node (ref "C49") (pin "2") (pinfunction "2_2") (pintype "passive"))
      (node (ref "C50") (pin "2") (pinfunction "2_2") (pintype "passive"))
      (node (ref "IC1") (pin "104") (pinfunction "GNDIO3-1_104") (pintype "power_in"))
      (node (ref "IC1") (pin "119") (pinfunction "GNDIO3-2_119") (pintype "power_in"))
      (node (ref "IC1") (pin "37") (pinfunction "GNDANA_37") (pintype "power_in"))
      (node (ref "IC1") (pin "52") (pinfunction "GNDPLL_52") (pintype "power_in"))
      (node (ref "IC1") (pin "56") (pinfunction "GNDCORE_56") (pintype "power_in"))
      (node (ref "IC1") (pin "6") (pinfunction "GNDIO1_6") (pintype "power_in"))
      (node (ref "IC1") (pin "76") (pinfunction "GNDIO2_76") (pintype "power_in"))
      (node (ref "J1") (pin "10") (pinfunction "10_10") (pintype "passive"))
      (node (ref "J1") (pin "12") (pinfunction "12_12") (pintype "passive"))
      (node (ref "J1") (pin "14") (pinfunction "14_14") (pintype "passive"))
      (node (ref "J1") (pin "16") (pinfunction "16_16") (pintype "passive"))
      (node (ref "J1") (pin "2") (pinfunction "2_2") (pintype "passive"))
      (node (ref "J1") (pin "4") (pinfunction "4_4") (pintype "passive"))
      (node (ref "J1") (pin "6") (pinfunction "6_6") (pintype "passive"))
      (node (ref "J1") (pin "8") (pinfunction "8_8") (pintype "passive"))
      (node (ref "J18") (pin "10") (pinfunction "10_10") (pintype "passive"))
      (node (ref "J18") (pin "2") (pinfunction "2_2") (pintype "passive"))
      (node (ref "J19") (pin "9") (pinfunction "9_9") (pintype "passive"))
      (node (ref "J2") (pin "10") (pinfunction "10_10") (pintype "passive"))
      (node (ref "J2") (pin "12") (pinfunction "12_12") (pintype "passive"))
      (node (ref "J2") (pin "14") (pinfunction "14_14") (pintype "passive"))
      (node (ref "J2") (pin "16") (pinfunction "16_16") (pintype "passive"))
      (node (ref "J2") (pin "2") (pinfunction "2_2") (pintype "passive"))
      (node (ref "J2") (pin "4") (pinfunction "4_4") (pintype "passive"))
      (node (ref "J2") (pin "6") (pinfunction "6_6") (pintype "passive"))
      (node (ref "J2") (pin "8") (pinfunction "8_8") (pintype "passive"))
      (node (ref "J3") (pin "10") (pinfunction "10_10") (pintype "passive"))
      (node (ref "J3") (pin "12") (pinfunction "12_12") (pintype "passive"))
      (node (ref "J3") (pin "14") (pinfunction "14_14") (pintype "passive"))
      (node (ref "J3") (pin "16") (pinfunction "16_16") (pintype "passive"))
      (node (ref "J3") (pin "2") (pinfunction "2_2") (pintype "passive"))
      (node (ref "J3") (pin "4") (pinfunction "4_4") (pintype "passive"))
      (node (ref "J3") (pin "6") (pinfunction "6_6") (pintype "passive"))
      (node (ref "J3") (pin "8") (pinfunction "8_8") (pintype "passive"))
      (node (ref "J4") (pin "10") (pinfunction "10_10") (pintype "passive"))
      (node (ref "J4") (pin "12") (pinfunction "12_12") (pintype "passive"))
      (node (ref "J4") (pin "14") (pinfunction "14_14") (pintype "passive"))
      (node (ref "J4") (pin "16") (pinfunction "16_16") (pintype "passive"))
      (node (ref "J4") (pin "2") (pinfunction "2_2") (pintype "passive"))
      (node (ref "J4") (pin "4") (pinfunction "4_4") (pintype "passive"))
      (node (ref "J4") (pin "6") (pinfunction "6_6") (pintype "passive"))
      (node (ref "J4") (pin "8") (pinfunction "8_8") (pintype "passive"))
      (node (ref "JP1") (pin "3") (pinfunction "3_3") (pintype "passive"))
      (node (ref "LED1") (pin "C") (pinfunction "C_C") (pintype "passive"))
      (node (ref "LED2") (pin "C") (pinfunction "C_C") (pintype "passive"))
      (node (ref "S1") (pin "1") (pinfunction "1_1") (pintype "passive"))
      (node (ref "S1") (pin "2") (pinfunction "2_2") (pintype "passive"))
      (node (ref "U1") (pin "GND_1") (pinfunction "GND_1_GND_1") (pintype "bidirectional"))
      (node (ref "U1") (pin "GND_2") (pinfunction "GND_2_GND_2") (pintype "bidirectional"))
      (node (ref "X1") (pin "4") (pinfunction "4_4") (pintype "passive"))
    )
    (net (code "130") (name "Net-(IC1-ADCVREFN)") (class "Default")
      (node (ref "C51") (pin "1") (pinfunction "1_1") (pintype "passive"))
      (node (ref "C52") (pin "1") (pinfunction "1_1") (pintype "passive"))
      (node (ref "IC1") (pin "35") (pinfunction "ADCVREFN_35") (pintype "input"))
    )
    (net (code "131") (name "Net-(IC1-ADCVREFP)") (class "Default")
      (node (ref "C51") (pin "2") (pinfunction "2_2") (pintype "passive"))
      (node (ref "C52") (pin "2") (pinfunction "2_2") (pintype "passive"))
      (node (ref "IC1") (pin "34") (pinfunction "ADCVREFP_34") (pintype "input"))
    )
    (net (code "132") (name "Net-(IC1-DM)") (class "Default")
      (node (ref "IC1") (pin "50") (pinfunction "DM_50") (pintype "bidirectional"))
      (node (ref "R1") (pin "1") (pinfunction "1_1") (pintype "passive"))
    )
    (net (code "133") (name "Net-(IC1-DP)") (class "Default")
      (node (ref "IC1") (pin "51") (pinfunction "DP_51") (pintype "bidirectional"))
      (node (ref "R2") (pin "1") (pinfunction "1_1") (pintype "passive"))
    )
    (net (code "134") (name "Net-(IC1-PA04)") (class "Default")
      (node (ref "IC1") (pin "21") (pinfunction "PA04_21") (pintype "bidirectional"))
      (node (ref "R33") (pin "2") (pinfunction "2_2") (pintype "passive"))
    )
    (net (code "135") (name "Net-(IC1-PA05)") (class "Default")
      (node (ref "IC1") (pin "22") (pinfunction "PA05_22") (pintype "bidirectional"))
      (node (ref "R34") (pin "2") (pinfunction "2_2") (pintype "passive"))
    )
    (net (code "136") (name "Net-(IC1-PD02)") (class "Default")
      (node (ref "IC1") (pin "109") (pinfunction "PD02_109") (pintype "bidirectional"))
      (node (ref "JP1") (pin "2") (pinfunction "2_2") (pintype "passive"))
    )
    (net (code "137") (name "Net-(IC1-VDDCORE)") (class "Default")
      (node (ref "C37") (pin "1") (pinfunction "1_1") (pintype "passive"))
      (node (ref "C38") (pin "1") (pinfunction "1_1") (pintype "passive"))
      (node (ref "IC1") (pin "55") (pinfunction "VDDCORE_55") (pintype "power_in"))
    )
    (net (code "138") (name "Net-(IC1-VDDIN_33)") (class "Default")
      (node (ref "C35") (pin "1") (pinfunction "1_1") (pintype "passive"))
      (node (ref "C36") (pin "1") (pinfunction "1_1") (pintype "passive"))
      (node (ref "IC1") (pin "54") (pinfunction "VDDIN_33_54") (pintype "power_in"))
    )
    (net (code "139") (name "Net-(J1-Pad1)") (class "Default")
      (node (ref "J1") (pin "1") (pinfunction "1_1") (pintype "passive"))
      (node (ref "J5") (pin "2") (pinfunction "2_2") (pintype "passive"))
    )
    (net (code "140") (name "Net-(J1-Pad3)") (class "Default")
      (node (ref "J1") (pin "3") (pinfunction "3_3") (pintype "passive"))
      (node (ref "J5") (pin "4") (pinfunction "4_4") (pintype "passive"))
    )
    (net (code "141") (name "Net-(J1-Pad5)") (class "Default")
      (node (ref "J1") (pin "5") (pinfunction "5_5") (pintype "passive"))
      (node (ref "J5") (pin "6") (pinfunction "6_6") (pintype "passive"))
    )
    (net (code "142") (name "Net-(J1-Pad7)") (class "Default")
      (node (ref "J1") (pin "7") (pinfunction "7_7") (pintype "passive"))
      (node (ref "J5") (pin "8") (pinfunction "8_8") (pintype "passive"))
    )
    (net (code "143") (name "Net-(J1-Pad9)") (class "Default")
      (node (ref "J1") (pin "9") (pinfunction "9_9") (pintype "passive"))
      (node (ref "J5") (pin "10") (pinfunction "10_10") (pintype "passive"))
    )
    (net (code "144") (name "Net-(J1-Pad11)") (class "Default")
      (node (ref "J1") (pin "11") (pinfunction "11_11") (pintype "passive"))
      (node (ref "J5") (pin "12") (pinfunction "12_12") (pintype "passive"))
    )
    (net (code "145") (name "Net-(J1-Pad13)") (class "Default")
      (node (ref "J1") (pin "13") (pinfunction "13_13") (pintype "passive"))
      (node (ref "J5") (pin "14") (pinfunction "14_14") (pintype "passive"))
    )
    (net (code "146") (name "Net-(J1-Pad15)") (class "Default")
      (node (ref "J1") (pin "15") (pinfunction "15_15") (pintype "passive"))
      (node (ref "J5") (pin "16") (pinfunction "16_16") (pintype "passive"))
    )
    (net (code "147") (name "Net-(J2-Pad1)") (class "Default")
      (node (ref "J2") (pin "1") (pinfunction "1_1") (pintype "passive"))
      (node (ref "J6") (pin "2") (pinfunction "2_2") (pintype "passive"))
    )
    (net (code "148") (name "Net-(J2-Pad3)") (class "Default")
      (node (ref "J2") (pin "3") (pinfunction "3_3") (pintype "passive"))
      (node (ref "J6") (pin "4") (pinfunction "4_4") (pintype "passive"))
    )
    (net (code "149") (name "Net-(J2-Pad5)") (class "Default")
      (node (ref "J2") (pin "5") (pinfunction "5_5") (pintype "passive"))
      (node (ref "J6") (pin "6") (pinfunction "6_6") (pintype "passive"))
    )
    (net (code "150") (name "Net-(J2-Pad7)") (class "Default")
      (node (ref "J2") (pin "7") (pinfunction "7_7") (pintype "passive"))
      (node (ref "J6") (pin "8") (pinfunction "8_8") (pintype "passive"))
    )
    (net (code "151") (name "Net-(J2-Pad9)") (class "Default")
      (node (ref "J2") (pin "9") (pinfunction "9_9") (pintype "passive"))
      (node (ref "J6") (pin "10") (pinfunction "10_10") (pintype "passive"))
    )
    (net (code "152") (name "Net-(J2-Pad11)") (class "Default")
      (node (ref "J2") (pin "11") (pinfunction "11_11") (pintype "passive"))
      (node (ref "J6") (pin "12") (pinfunction "12_12") (pintype "passive"))
    )
    (net (code "153") (name "Net-(J2-Pad13)") (class "Default")
      (node (ref "J2") (pin "13") (pinfunction "13_13") (pintype "passive"))
      (node (ref "J6") (pin "14") (pinfunction "14_14") (pintype "passive"))
    )
    (net (code "154") (name "Net-(J2-Pad15)") (class "Default")
      (node (ref "J2") (pin "15") (pinfunction "15_15") (pintype "passive"))
      (node (ref "J6") (pin "16") (pinfunction "16_16") (pintype "passive"))
    )
    (net (code "155") (name "Net-(J3-Pad1)") (class "Default")
      (node (ref "J3") (pin "1") (pinfunction "1_1") (pintype "passive"))
      (node (ref "J7") (pin "2") (pinfunction "2_2") (pintype "passive"))
    )
    (net (code "156") (name "Net-(J3-Pad3)") (class "Default")
      (node (ref "J3") (pin "3") (pinfunction "3_3") (pintype "passive"))
      (node (ref "J7") (pin "4") (pinfunction "4_4") (pintype "passive"))
    )
    (net (code "157") (name "Net-(J3-Pad5)") (class "Default")
      (node (ref "J3") (pin "5") (pinfunction "5_5") (pintype "passive"))
      (node (ref "J7") (pin "6") (pinfunction "6_6") (pintype "passive"))
    )
    (net (code "158") (name "Net-(J3-Pad7)") (class "Default")
      (node (ref "J3") (pin "7") (pinfunction "7_7") (pintype "passive"))
      (node (ref "J7") (pin "8") (pinfunction "8_8") (pintype "passive"))
    )
    (net (code "159") (name "Net-(J3-Pad9)") (class "Default")
      (node (ref "J3") (pin "9") (pinfunction "9_9") (pintype "passive"))
      (node (ref "J7") (pin "10") (pinfunction "10_10") (pintype "passive"))
    )
    (net (code "160") (name "Net-(J3-Pad11)") (class "Default")
      (node (ref "J3") (pin "11") (pinfunction "11_11") (pintype "passive"))
      (node (ref "J7") (pin "12") (pinfunction "12_12") (pintype "passive"))
    )
    (net (code "161") (name "Net-(J3-Pad13)") (class "Default")
      (node (ref "J3") (pin "13") (pinfunction "13_13") (pintype "passive"))
      (node (ref "J7") (pin "14") (pinfunction "14_14") (pintype "passive"))
    )
    (net (code "162") (name "Net-(J3-Pad15)") (class "Default")
      (node (ref "J3") (pin "15") (pinfunction "15_15") (pintype "passive"))
      (node (ref "J7") (pin "16") (pinfunction "16_16") (pintype "passive"))
    )
    (net (code "163") (name "Net-(J4-Pad1)") (class "Default")
      (node (ref "J4") (pin "1") (pinfunction "1_1") (pintype "passive"))
      (node (ref "J8") (pin "2") (pinfunction "2_2") (pintype "passive"))
    )
    (net (code "164") (name "Net-(J4-Pad3)") (class "Default")
      (node (ref "J4") (pin "3") (pinfunction "3_3") (pintype "passive"))
      (node (ref "J8") (pin "4") (pinfunction "4_4") (pintype "passive"))
    )
    (net (code "165") (name "Net-(J4-Pad5)") (class "Default")
      (node (ref "J4") (pin "5") (pinfunction "5_5") (pintype "passive"))
      (node (ref "J8") (pin "6") (pinfunction "6_6") (pintype "passive"))
    )
    (net (code "166") (name "Net-(J4-Pad7)") (class "Default")
      (node (ref "J4") (pin "7") (pinfunction "7_7") (pintype "passive"))
      (node (ref "J8") (pin "8") (pinfunction "8_8") (pintype "passive"))
    )
    (net (code "167") (name "Net-(J4-Pad9)") (class "Default")
      (node (ref "J4") (pin "9") (pinfunction "9_9") (pintype "passive"))
      (node (ref "J8") (pin "10") (pinfunction "10_10") (pintype "passive"))
    )
    (net (code "168") (name "Net-(J4-Pad11)") (class "Default")
      (node (ref "J4") (pin "11") (pinfunction "11_11") (pintype "passive"))
      (node (ref "J8") (pin "12") (pinfunction "12_12") (pintype "passive"))
    )
    (net (code "169") (name "Net-(J4-Pad13)") (class "Default")
      (node (ref "J4") (pin "13") (pinfunction "13_13") (pintype "passive"))
      (node (ref "J8") (pin "14") (pinfunction "14_14") (pintype "passive"))
    )
    (net (code "170") (name "Net-(J4-Pad15)") (class "Default")
      (node (ref "J4") (pin "15") (pinfunction "15_15") (pintype "passive"))
      (node (ref "J8") (pin "16") (pinfunction "16_16") (pintype "passive"))
    )
    (net (code "171") (name "Net-(LED1-PadA)") (class "Default")
      (node (ref "LED1") (pin "A") (pinfunction "A_A") (pintype "passive"))
      (node (ref "R33") (pin "1") (pinfunction "1_1") (pintype "passive"))
    )
    (net (code "172") (name "Net-(LED2-PadA)") (class "Default")
      (node (ref "LED2") (pin "A") (pinfunction "A_A") (pintype "passive"))
      (node (ref "R34") (pin "1") (pinfunction "1_1") (pintype "passive"))
    )
    (net (code "173") (name "Net-(R1-Pad2)") (class "Default")
      (node (ref "R1") (pin "2") (pinfunction "2_2") (pintype "passive"))
      (node (ref "X1") (pin "2") (pinfunction "2_2") (pintype "passive"))
    )
    (net (code "174") (name "Net-(R2-Pad2)") (class "Default")
      (node (ref "R2") (pin "2") (pinfunction "2_2") (pintype "passive"))
      (node (ref "X1") (pin "3") (pinfunction "3_3") (pintype "passive"))
    )
    (net (code "175") (name "Net-(SJ5-Pad1)") (class "Default")
      (node (ref "SJ5") (pin "1") (pinfunction "1_1") (pintype "passive"))
      (node (ref "U1") (pin "RESET") (pinfunction "RESET_RESET") (pintype "bidirectional"))
    )
    (net (code "176") (name "Net-(U1-0(RX0))") (class "Default")
      (node (ref "J15") (pin "3") (pinfunction "3_3") (pintype "passive"))
      (node (ref "U1") (pin "RX_PWM00") (pinfunction "0(RX0)_RX_PWM00") (pintype "bidirectional"))
    )
    (net (code "177") (name "Net-(U1-1(TX0))") (class "Default")
      (node (ref "J15") (pin "1") (pinfunction "1_1") (pintype "passive"))
      (node (ref "U1") (pin "TX_PWM01") (pinfunction "1(TX0)_TX_PWM01") (pintype "bidirectional"))
    )
    (net (code "178") (name "Net-(U1-14(TX3))") (class "Default")
      (node (ref "J15") (pin "5") (pinfunction "5_5") (pintype "passive"))
      (node (ref "U1") (pin "TX3_14") (pinfunction "14(TX3)_TX3_14") (pintype "bidirectional"))
    )
    (net (code "179") (name "Net-(U1-15(RX3))") (class "Default")
      (node (ref "J15") (pin "7") (pinfunction "7_7") (pintype "passive"))
      (node (ref "U1") (pin "RX3_15") (pinfunction "15(RX3)_RX3_15") (pintype "bidirectional"))
    )
    (net (code "180") (name "Net-(U1-16(TX2))") (class "Default")
      (node (ref "J15") (pin "9") (pinfunction "9_9") (pintype "passive"))
      (node (ref "U1") (pin "TX2_16") (pinfunction "16(TX2)_TX2_16") (pintype "bidirectional"))
    )
    (net (code "181") (name "Net-(U1-17(RX2))") (class "Default")
      (node (ref "J15") (pin "11") (pinfunction "11_11") (pintype "passive"))
      (node (ref "U1") (pin "RX2_17") (pinfunction "17(RX2)_RX2_17") (pintype "bidirectional"))
    )
    (net (code "182") (name "Net-(U1-18(TX1))") (class "Default")
      (node (ref "J15") (pin "13") (pinfunction "13_13") (pintype "passive"))
      (node (ref "U1") (pin "TX1_18") (pinfunction "18(TX1)_TX1_18") (pintype "bidirectional"))
    )
    (net (code "183") (name "Net-(U1-19(RX1))") (class "Default")
      (node (ref "J15") (pin "15") (pinfunction "15_15") (pintype "passive"))
      (node (ref "U1") (pin "RX1_19") (pinfunction "19(RX1)_RX1_19") (pintype "bidirectional"))
    )
    (net (code "184") (name "VCC") (class "Default")
      (node (ref "C1") (pin "+") (pinfunction "+_+") (pintype "passive"))
      (node (ref "C33") (pin "1") (pinfunction "1_1") (pintype "passive"))
      (node (ref "C34") (pin "1") (pinfunction "1_1") (pintype "passive"))
      (node (ref "C39") (pin "1") (pinfunction "1_1") (pintype "passive"))
      (node (ref "C40") (pin "1") (pinfunction "1_1") (pintype "passive"))
      (node (ref "C41") (pin "1") (pinfunction "1_1") (pintype "passive"))
      (node (ref "C42") (pin "1") (pinfunction "1_1") (pintype "passive"))
      (node (ref "C43") (pin "1") (pinfunction "1_1") (pintype "passive"))
      (node (ref "C44") (pin "1") (pinfunction "1_1") (pintype "passive"))
      (node (ref "C45") (pin "1") (pinfunction "1_1") (pintype "passive"))
      (node (ref "C46") (pin "1") (pinfunction "1_1") (pintype "passive"))
      (node (ref "C47") (pin "1") (pinfunction "1_1") (pintype "passive"))
      (node (ref "C48") (pin "1") (pinfunction "1_1") (pintype "passive"))
      (node (ref "C49") (pin "1") (pinfunction "1_1") (pintype "passive"))
      (node (ref "C50") (pin "1") (pinfunction "1_1") (pintype "passive"))
      (node (ref "IC1") (pin "103") (pinfunction "VDDIO3-1_103") (pintype "power_in"))
      (node (ref "IC1") (pin "118") (pinfunction "VDDIO3-2_118") (pintype "power_in"))
      (node (ref "IC1") (pin "38") (pinfunction "VDDANA_38") (pintype "power_in"))
      (node (ref "IC1") (pin "5") (pinfunction "VDDIO1_5") (pintype "power_in"))
      (node (ref "IC1") (pin "53") (pinfunction "VDDIN_5_53") (pintype "power_in"))
      (node (ref "IC1") (pin "75") (pinfunction "VDDIO2_75") (pintype "power_in"))
      (node (ref "J18") (pin "4") (pinfunction "4_4") (pintype "passive"))
      (node (ref "J19") (pin "10") (pinfunction "10_10") (pintype "passive"))
      (node (ref "JP1") (pin "1") (pinfunction "1_1") (pintype "passive"))
      (node (ref "R35") (pin "1") (pinfunction "1_1") (pintype "passive"))
      (node (ref "U1") (pin "5V_1") (pinfunction "5V_1_5V_1") (pintype "bidirectional"))
      (node (ref "X1") (pin "1") (pinfunction "1_1") (pintype "passive"))
    )
    (net (code "185") (name "unconnected-(IC1-PD07-Pad114)") (class "Default")
      (node (ref "IC1") (pin "114") (pinfunction "PD07_114") (pintype "bidirectional"))
    )
    (net (code "186") (name "unconnected-(IC1-PD08-Pad115)") (class "Default")
      (node (ref "IC1") (pin "115") (pinfunction "PD08_115") (pintype "bidirectional"))
    )
    (net (code "187") (name "unconnected-(IC1-PD09-Pad116)") (class "Default")
      (node (ref "IC1") (pin "116") (pinfunction "PD09_116") (pintype "bidirectional"))
    )
    (net (code "188") (name "unconnected-(IC1-PD10-Pad117)") (class "Default")
      (node (ref "IC1") (pin "117") (pinfunction "PD10_117") (pintype "bidirectional"))
    )
    (net (code "189") (name "unconnected-(IC1-PD25-Pad134)") (class "Default")
      (node (ref "IC1") (pin "134") (pinfunction "PD25_134") (pintype "bidirectional"))
    )
    (net (code "190") (name "unconnected-(IC1-PD26-Pad135)") (class "Default")
      (node (ref "IC1") (pin "135") (pinfunction "PD26_135") (pintype "bidirectional"))
    )
    (net (code "191") (name "unconnected-(IC1-PD27-Pad136)") (class "Default")
      (node (ref "IC1") (pin "136") (pinfunction "PD27_136") (pintype "bidirectional"))
    )
    (net (code "192") (name "unconnected-(IC1-PD28-Pad137)") (class "Default")
      (node (ref "IC1") (pin "137") (pinfunction "PD28_137") (pintype "bidirectional"))
    )
    (net (code "193") (name "unconnected-(IC1-PD29-Pad138)") (class "Default")
      (node (ref "IC1") (pin "138") (pinfunction "PD29_138") (pintype "bidirectional"))
    )
    (net (code "194") (name "unconnected-(IC1-PD30-Pad139)") (class "Default")
      (node (ref "IC1") (pin "139") (pinfunction "PD30_139") (pintype "bidirectional"))
    )
    (net (code "195") (name "unconnected-(IC1-VBUS-Pad49)") (class "Default")
      (node (ref "IC1") (pin "49") (pinfunction "VBUS_49") (pintype "input"))
    )
    (net (code "196") (name "unconnected-(J18-Pad7)") (class "Default")
      (node (ref "J18") (pin "7") (pinfunction "7_7") (pintype "passive"))
    )
    (net (code "197") (name "unconnected-(J18-Pad8)") (class "Default")
      (node (ref "J18") (pin "8") (pinfunction "8_8") (pintype "passive"))
    )
    (net (code "198") (name "unconnected-(J19-Pad1)") (class "Default")
      (node (ref "J19") (pin "1") (pinfunction "1_1") (pintype "passive"))
    )
    (net (code "199") (name "unconnected-(J19-Pad2)") (class "Default")
      (node (ref "J19") (pin "2") (pinfunction "2_2") (pintype "passive"))
    )
    (net (code "200") (name "unconnected-(J19-Pad3)") (class "Default")
      (node (ref "J19") (pin "3") (pinfunction "3_3") (pintype "passive"))
    )
    (net (code "201") (name "unconnected-(J19-Pad4)") (class "Default")
      (node (ref "J19") (pin "4") (pinfunction "4_4") (pintype "passive"))
    )
    (net (code "202") (name "unconnected-(U1-2-PadPWM02)") (class "Default")
      (node (ref "U1") (pin "PWM02") (pinfunction "2_PWM02") (pintype "bidirectional"))
    )
    (net (code "203") (name "unconnected-(U1-3-PadPWM03)") (class "Default")
      (node (ref "U1") (pin "PWM03") (pinfunction "3_PWM03") (pintype "bidirectional"))
    )
    (net (code "204") (name "unconnected-(U1-3.3V-Pad3V3)") (class "Default")
      (node (ref "U1") (pin "3V3") (pinfunction "3.3V_3V3") (pintype "bidirectional"))
    )
    (net (code "205") (name "unconnected-(U1-4-PadPWM04)") (class "Default")
      (node (ref "U1") (pin "PWM04") (pinfunction "4_PWM04") (pintype "bidirectional"))
    )
    (net (code "206") (name "unconnected-(U1-5-PadPWM05)") (class "Default")
      (node (ref "U1") (pin "PWM05") (pinfunction "5_PWM05") (pintype "bidirectional"))
    )
    (net (code "207") (name "unconnected-(U1-6-PadPWM06)") (class "Default")
      (node (ref "U1") (pin "PWM06") (pinfunction "6_PWM06") (pintype "bidirectional"))
    )
    (net (code "208") (name "unconnected-(U1-7-PadPWM07)") (class "Default")
      (node (ref "U1") (pin "PWM07") (pinfunction "7_PWM07") (pintype "bidirectional"))
    )
    (net (code "209") (name "unconnected-(U1-8-PadPWM08)") (class "Default")
      (node (ref "U1") (pin "PWM08") (pinfunction "8_PWM08") (pintype "bidirectional"))
    )
    (net (code "210") (name "unconnected-(U1-9-PadPWM09)") (class "Default")
      (node (ref "U1") (pin "PWM09") (pinfunction "9_PWM09") (pintype "bidirectional"))
    )
    (net (code "211") (name "unconnected-(U1-20(SDA)-PadSCA_20)") (class "Default")
      (node (ref "U1") (pin "SCA_20") (pinfunction "20(SDA)_SCA_20") (pintype "bidirectional"))
    )
    (net (code "212") (name "unconnected-(U1-21(SCL)-PadSCL_21)") (class "Default")
      (node (ref "U1") (pin "SCL_21") (pinfunction "21(SCL)_SCL_21") (pintype "bidirectional"))
    )
    (net (code "213") (name "unconnected-(U1-A0-PadA00)") (class "Default")
      (node (ref "U1") (pin "A00") (pinfunction "A0_A00") (pintype "bidirectional"))
    )
    (net (code "214") (name "unconnected-(U1-A1-PadA01)") (class "Default")
      (node (ref "U1") (pin "A01") (pinfunction "A1_A01") (pintype "bidirectional"))
    )
    (net (code "215") (name "unconnected-(U1-A2-PadA02)") (class "Default")
      (node (ref "U1") (pin "A02") (pinfunction "A2_A02") (pintype "bidirectional"))
    )
    (net (code "216") (name "unconnected-(U1-A3-PadA03)") (class "Default")
      (node (ref "U1") (pin "A03") (pinfunction "A3_A03") (pintype "bidirectional"))
    )
    (net (code "217") (name "unconnected-(U1-A4-PadA04)") (class "Default")
      (node (ref "U1") (pin "A04") (pinfunction "A4_A04") (pintype "bidirectional"))
    )
    (net (code "218") (name "unconnected-(U1-A5-PadA05)") (class "Default")
      (node (ref "U1") (pin "A05") (pinfunction "A5_A05") (pintype "bidirectional"))
    )
    (net (code "219") (name "unconnected-(U1-A6-PadA06)") (class "Default")
      (node (ref "U1") (pin "A06") (pinfunction "A6_A06") (pintype "bidirectional"))
    )
    (net (code "220") (name "unconnected-(U1-A7-PadA07)") (class "Default")
      (node (ref "U1") (pin "A07") (pinfunction "A7_A07") (pintype "bidirectional"))
    )
    (net (code "221") (name "unconnected-(U1-A8-PadA08)") (class "Default")
      (node (ref "U1") (pin "A08") (pinfunction "A8_A08") (pintype "bidirectional"))
    )
    (net (code "222") (name "unconnected-(U1-A9-PadA09)") (class "Default")
      (node (ref "U1") (pin "A09") (pinfunction "A9_A09") (pintype "bidirectional"))
    )
    (net (code "223") (name "unconnected-(U1-Pad5V_2)") (class "Default")
      (node (ref "U1") (pin "5V_2") (pinfunction "5V_2_5V_2") (pintype "bidirectional"))
    )
    (net (code "224") (name "unconnected-(U1-Pad5V_3)") (class "Default")
      (node (ref "U1") (pin "5V_3") (pinfunction "5V_3_5V_3") (pintype "bidirectional"))
    )
    (net (code "225") (name "unconnected-(U1-Pad22)") (class "Default")
      (node (ref "U1") (pin "22") (pinfunction "22_22") (pintype "bidirectional"))
    )
    (net (code "226") (name "unconnected-(U1-Pad23)") (class "Default")
      (node (ref "U1") (pin "23") (pinfunction "23_23") (pintype "bidirectional"))
    )
    (net (code "227") (name "unconnected-(U1-Pad24)") (class "Default")
      (node (ref "U1") (pin "24") (pinfunction "24_24") (pintype "bidirectional"))
    )
    (net (code "228") (name "unconnected-(U1-Pad25)") (class "Default")
      (node (ref "U1") (pin "25") (pinfunction "25_25") (pintype "bidirectional"))
    )
    (net (code "229") (name "unconnected-(U1-Pad26)") (class "Default")
      (node (ref "U1") (pin "26") (pinfunction "26_26") (pintype "bidirectional"))
    )
    (net (code "230") (name "unconnected-(U1-Pad27)") (class "Default")
      (node (ref "U1") (pin "27") (pinfunction "27_27") (pintype "bidirectional"))
    )
    (net (code "231") (name "unconnected-(U1-Pad28)") (class "Default")
      (node (ref "U1") (pin "28") (pinfunction "28_28") (pintype "bidirectional"))
    )
    (net (code "232") (name "unconnected-(U1-Pad29)") (class "Default")
      (node (ref "U1") (pin "29") (pinfunction "29_29") (pintype "bidirectional"))
    )
    (net (code "233") (name "unconnected-(U1-Pad30)") (class "Default")
      (node (ref "U1") (pin "30") (pinfunction "30_30") (pintype "bidirectional"))
    )
    (net (code "234") (name "unconnected-(U1-Pad31)") (class "Default")
      (node (ref "U1") (pin "31") (pinfunction "31_31") (pintype "bidirectional"))
    )
    (net (code "235") (name "unconnected-(U1-Pad32)") (class "Default")
      (node (ref "U1") (pin "32") (pinfunction "32_32") (pintype "bidirectional"))
    )
    (net (code "236") (name "unconnected-(U1-Pad33)") (class "Default")
      (node (ref "U1") (pin "33") (pinfunction "33_33") (pintype "bidirectional"))
    )
    (net (code "237") (name "unconnected-(U1-Pad34)") (class "Default")
      (node (ref "U1") (pin "34") (pinfunction "34_34") (pintype "bidirectional"))
    )
    (net (code "238") (name "unconnected-(U1-Pad35)") (class "Default")
      (node (ref "U1") (pin "35") (pinfunction "35_35") (pintype "bidirectional"))
    )
    (net (code "239") (name "unconnected-(U1-Pad36)") (class "Default")
      (node (ref "U1") (pin "36") (pinfunction "36_36") (pintype "bidirectional"))
    )
    (net (code "240") (name "unconnected-(U1-Pad37)") (class "Default")
      (node (ref "U1") (pin "37") (pinfunction "37_37") (pintype "bidirectional"))
    )
    (net (code "241") (name "unconnected-(U1-Pad38)") (class "Default")
      (node (ref "U1") (pin "38") (pinfunction "38_38") (pintype "bidirectional"))
    )
    (net (code "242") (name "unconnected-(U1-Pad39)") (class "Default")
      (node (ref "U1") (pin "39") (pinfunction "39_39") (pintype "bidirectional"))
    )
    (net (code "243") (name "unconnected-(U1-Pad40)") (class "Default")
      (node (ref "U1") (pin "40") (pinfunction "40_40") (pintype "bidirectional"))
    )
    (net (code "244") (name "unconnected-(U1-Pad41)") (class "Default")
      (node (ref "U1") (pin "41") (pinfunction "41_41") (pintype "bidirectional"))
    )
    (net (code "245") (name "unconnected-(U1-Pad42)") (class "Default")
      (node (ref "U1") (pin "42") (pinfunction "42_42") (pintype "bidirectional"))
    )
    (net (code "246") (name "unconnected-(U1-Pad43)") (class "Default")
      (node (ref "U1") (pin "43") (pinfunction "43_43") (pintype "bidirectional"))
    )
    (net (code "247") (name "unconnected-(U1-Pad44)") (class "Default")
      (node (ref "U1") (pin "44") (pinfunction "44_44") (pintype "bidirectional"))
    )
    (net (code "248") (name "unconnected-(U1-Pad45)") (class "Default")
      (node (ref "U1") (pin "45") (pinfunction "45_45") (pintype "bidirectional"))
    )
    (net (code "249") (name "unconnected-(U1-Pad46)") (class "Default")
      (node (ref "U1") (pin "46") (pinfunction "46_46") (pintype "bidirectional"))
    )
    (net (code "250") (name "unconnected-(U1-Pad47)") (class "Default")
      (node (ref "U1") (pin "47") (pinfunction "47_47") (pintype "bidirectional"))
    )
    (net (code "251") (name "unconnected-(U1-Pad48)") (class "Default")
      (node (ref "U1") (pin "48") (pinfunction "48_48") (pintype "bidirectional"))
    )
    (net (code "252") (name "unconnected-(U1-Pad49)") (class "Default")
      (node (ref "U1") (pin "49") (pinfunction "49_49") (pintype "bidirectional"))
    )
    (net (code "253") (name "unconnected-(U1-PadA10)") (class "Default")
      (node (ref "U1") (pin "A10") (pinfunction "A10_A10") (pintype "bidirectional"))
    )
    (net (code "254") (name "unconnected-(U1-PadA11)") (class "Default")
      (node (ref "U1") (pin "A11") (pinfunction "A11_A11") (pintype "bidirectional"))
    )
    (net (code "255") (name "unconnected-(U1-PadA12)") (class "Default")
      (node (ref "U1") (pin "A12") (pinfunction "A12_A12") (pintype "bidirectional"))
    )
    (net (code "256") (name "unconnected-(U1-PadA13)") (class "Default")
      (node (ref "U1") (pin "A13") (pinfunction "A13_A13") (pintype "bidirectional"))
    )
    (net (code "257") (name "unconnected-(U1-PadA14)") (class "Default")
      (node (ref "U1") (pin "A14") (pinfunction "A14_A14") (pintype "bidirectional"))
    )
    (net (code "258") (name "unconnected-(U1-PadA15)") (class "Default")
      (node (ref "U1") (pin "A15") (pinfunction "A15_A15") (pintype "bidirectional"))
    )
    (net (code "259") (name "unconnected-(U1-PadAREF)") (class "Default")
      (node (ref "U1") (pin "AREF") (pinfunction "AREF_AREF") (pintype "bidirectional"))
    )
    (net (code "260") (name "unconnected-(U1-PadGND_3)") (class "Default")
      (node (ref "U1") (pin "GND_3") (pinfunction "GND_3_GND_3") (pintype "bidirectional"))
    )
    (net (code "261") (name "unconnected-(U1-PadGND_4)") (class "Default")
      (node (ref "U1") (pin "GND_4") (pinfunction "GND_4_GND_4") (pintype "bidirectional"))
    )
    (net (code "262") (name "unconnected-(U1-PadGND_5)") (class "Default")
      (node (ref "U1") (pin "GND_5") (pinfunction "GND_5_GND_5") (pintype "bidirectional"))
    )
    (net (code "263") (name "unconnected-(U1-PadNC)") (class "Default")
      (node (ref "U1") (pin "NC") (pinfunction "NC_NC") (pintype "bidirectional"))
    )
    (net (code "264") (name "unconnected-(U1-PadSCA)") (class "Default")
      (node (ref "U1") (pin "SCA") (pinfunction "SCA_SCA") (pintype "bidirectional"))
    )
    (net (code "265") (name "unconnected-(U1-PadSCL)") (class "Default")
      (node (ref "U1") (pin "SCL") (pinfunction "SCL_SCL") (pintype "bidirectional"))
    )
    (net (code "266") (name "unconnected-(U1-PadVIN)") (class "Default")
      (node (ref "U1") (pin "VIN") (pinfunction "VIN_VIN") (pintype "bidirectional"))
    )
  )
)
